# projet666.net
KiCad netlist of a schematic drawn in EasyEDA Pro
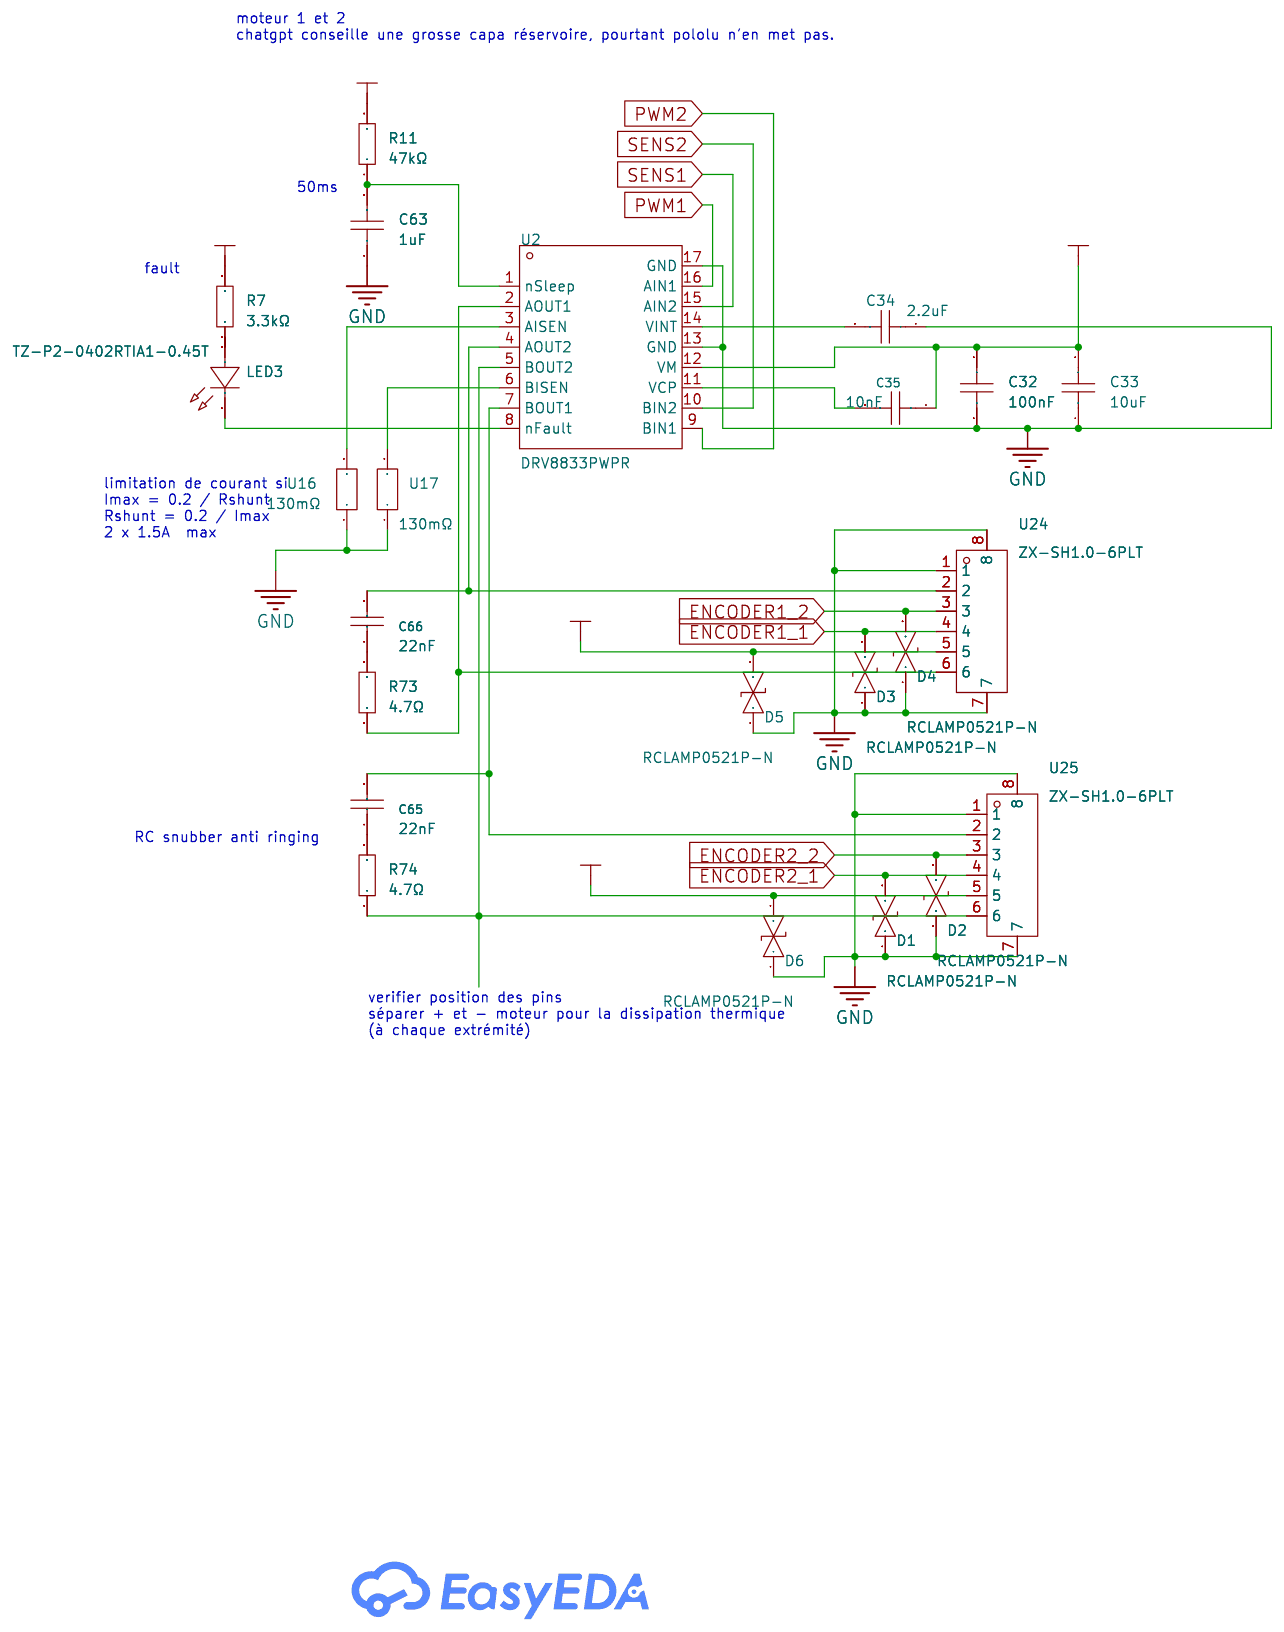
[diagram p0: Pont + connecteurs]
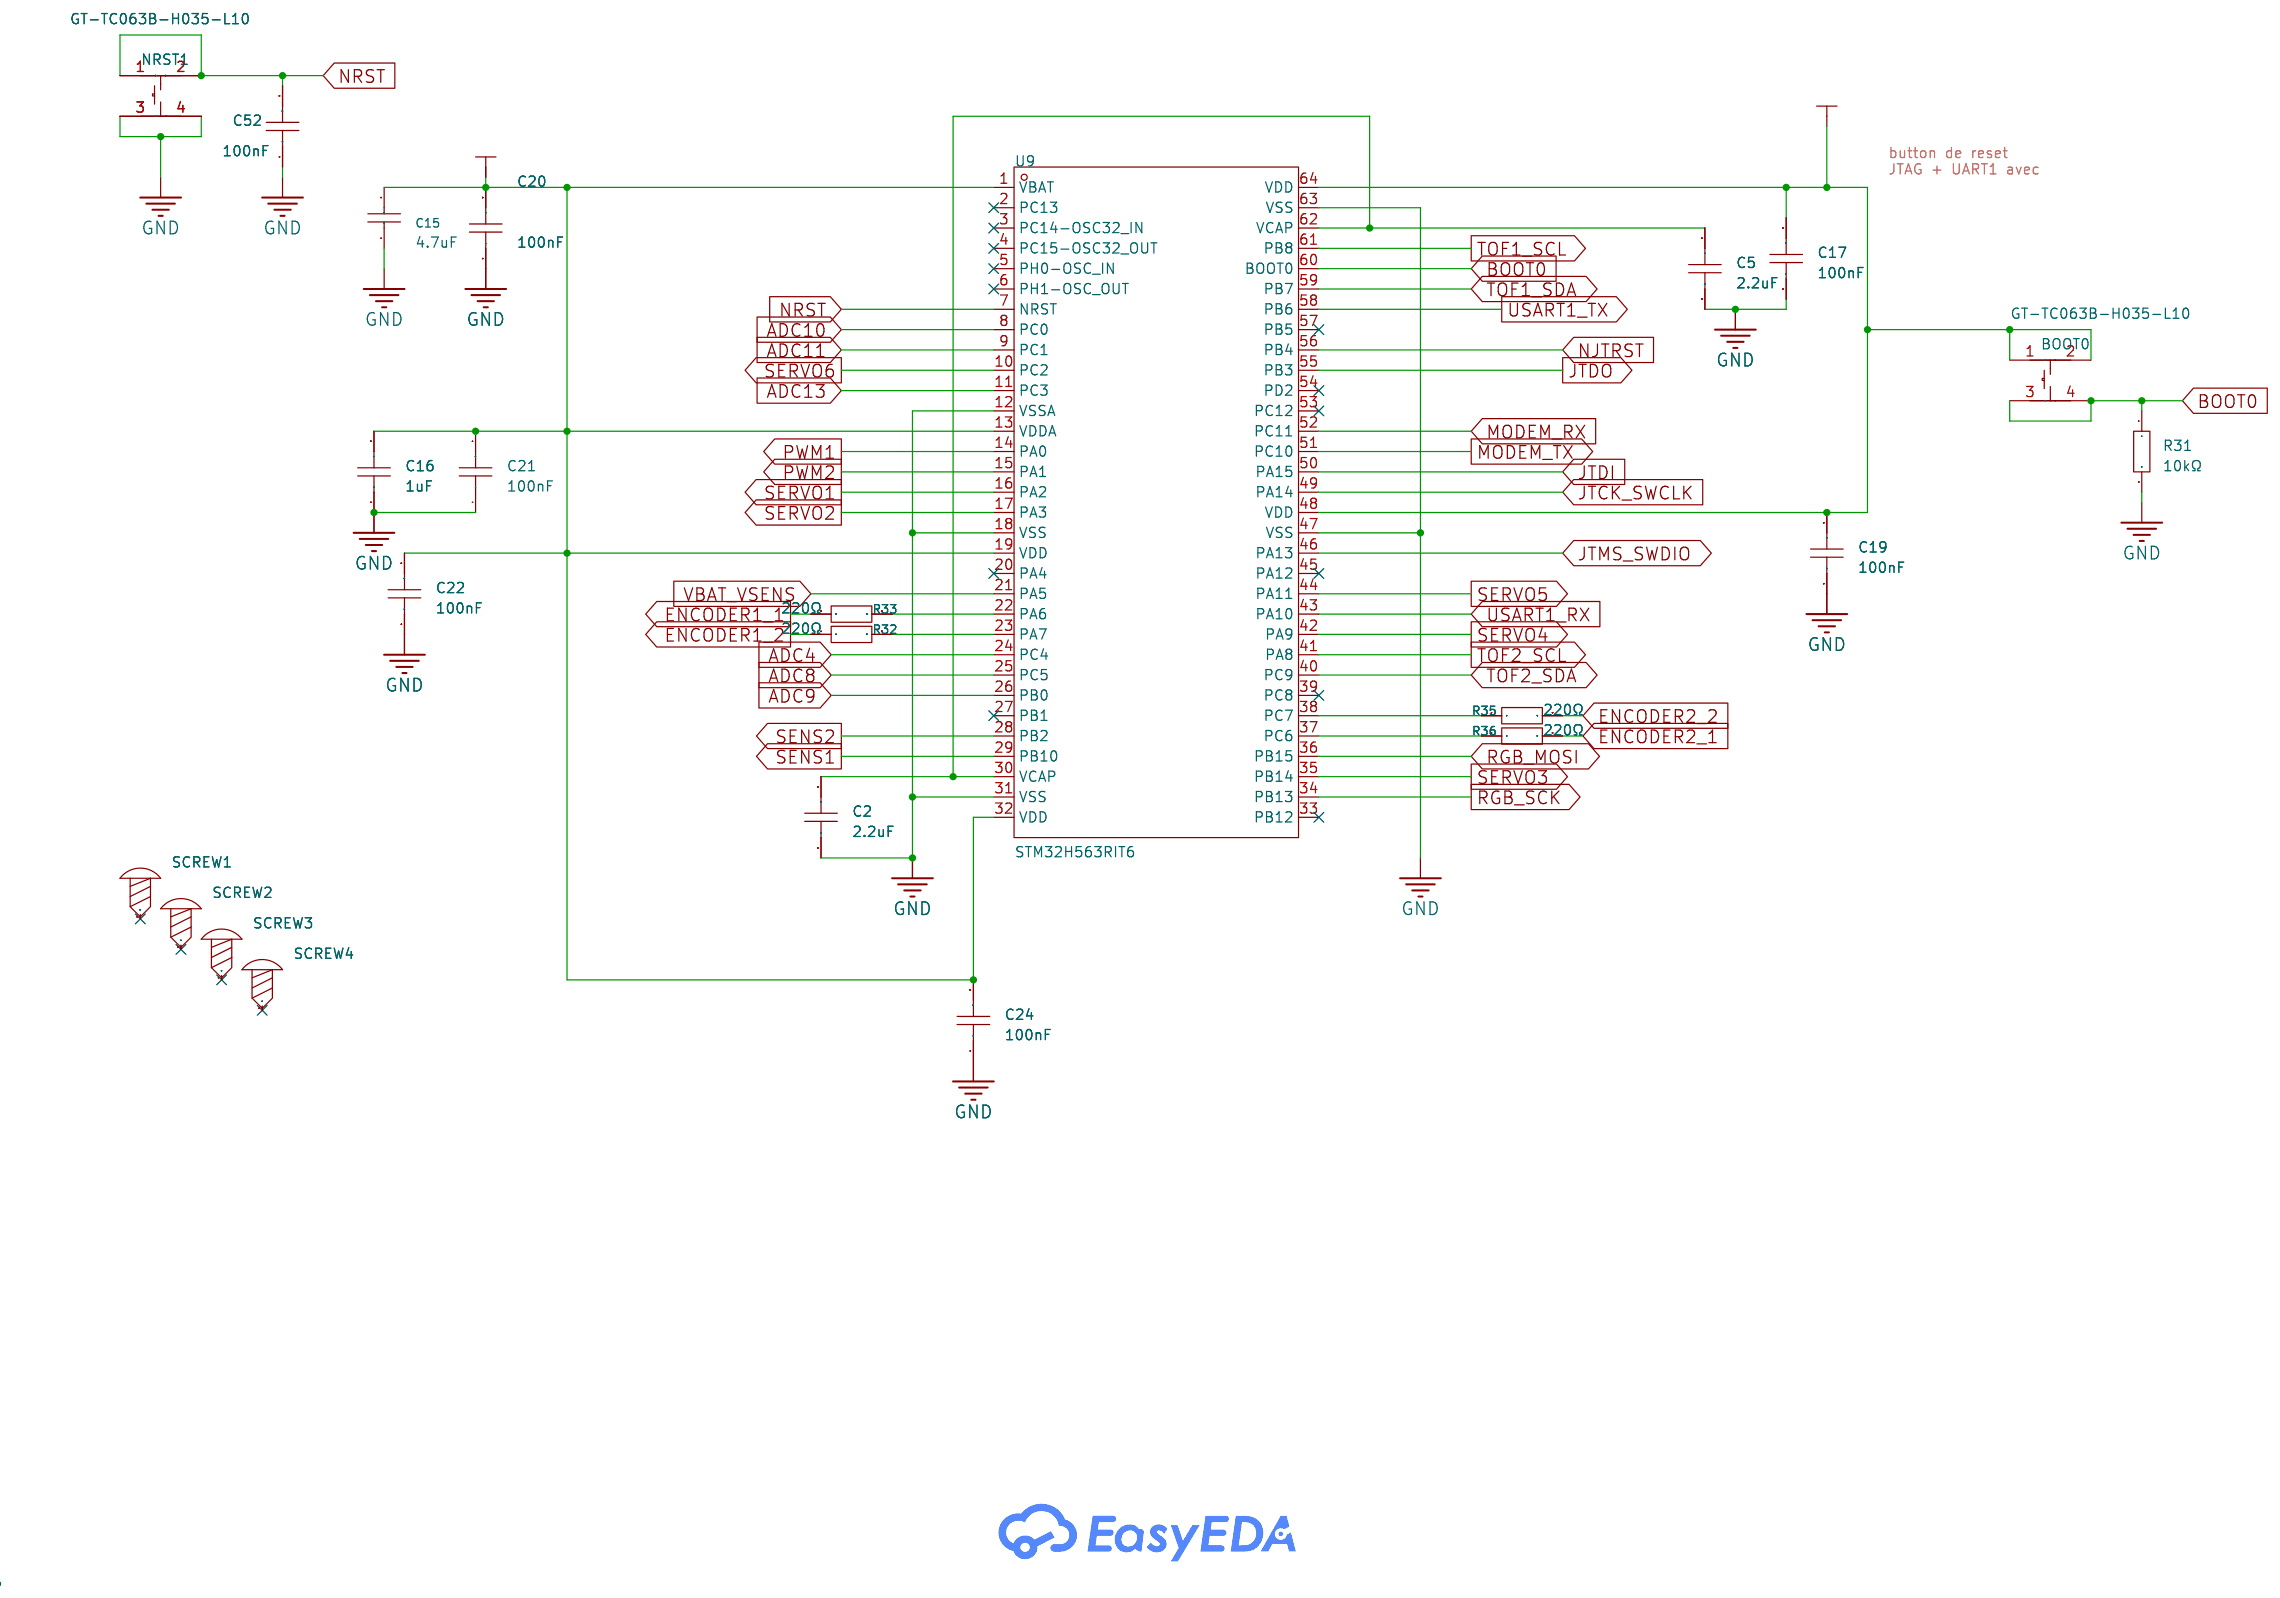
[diagram p1: stm32]
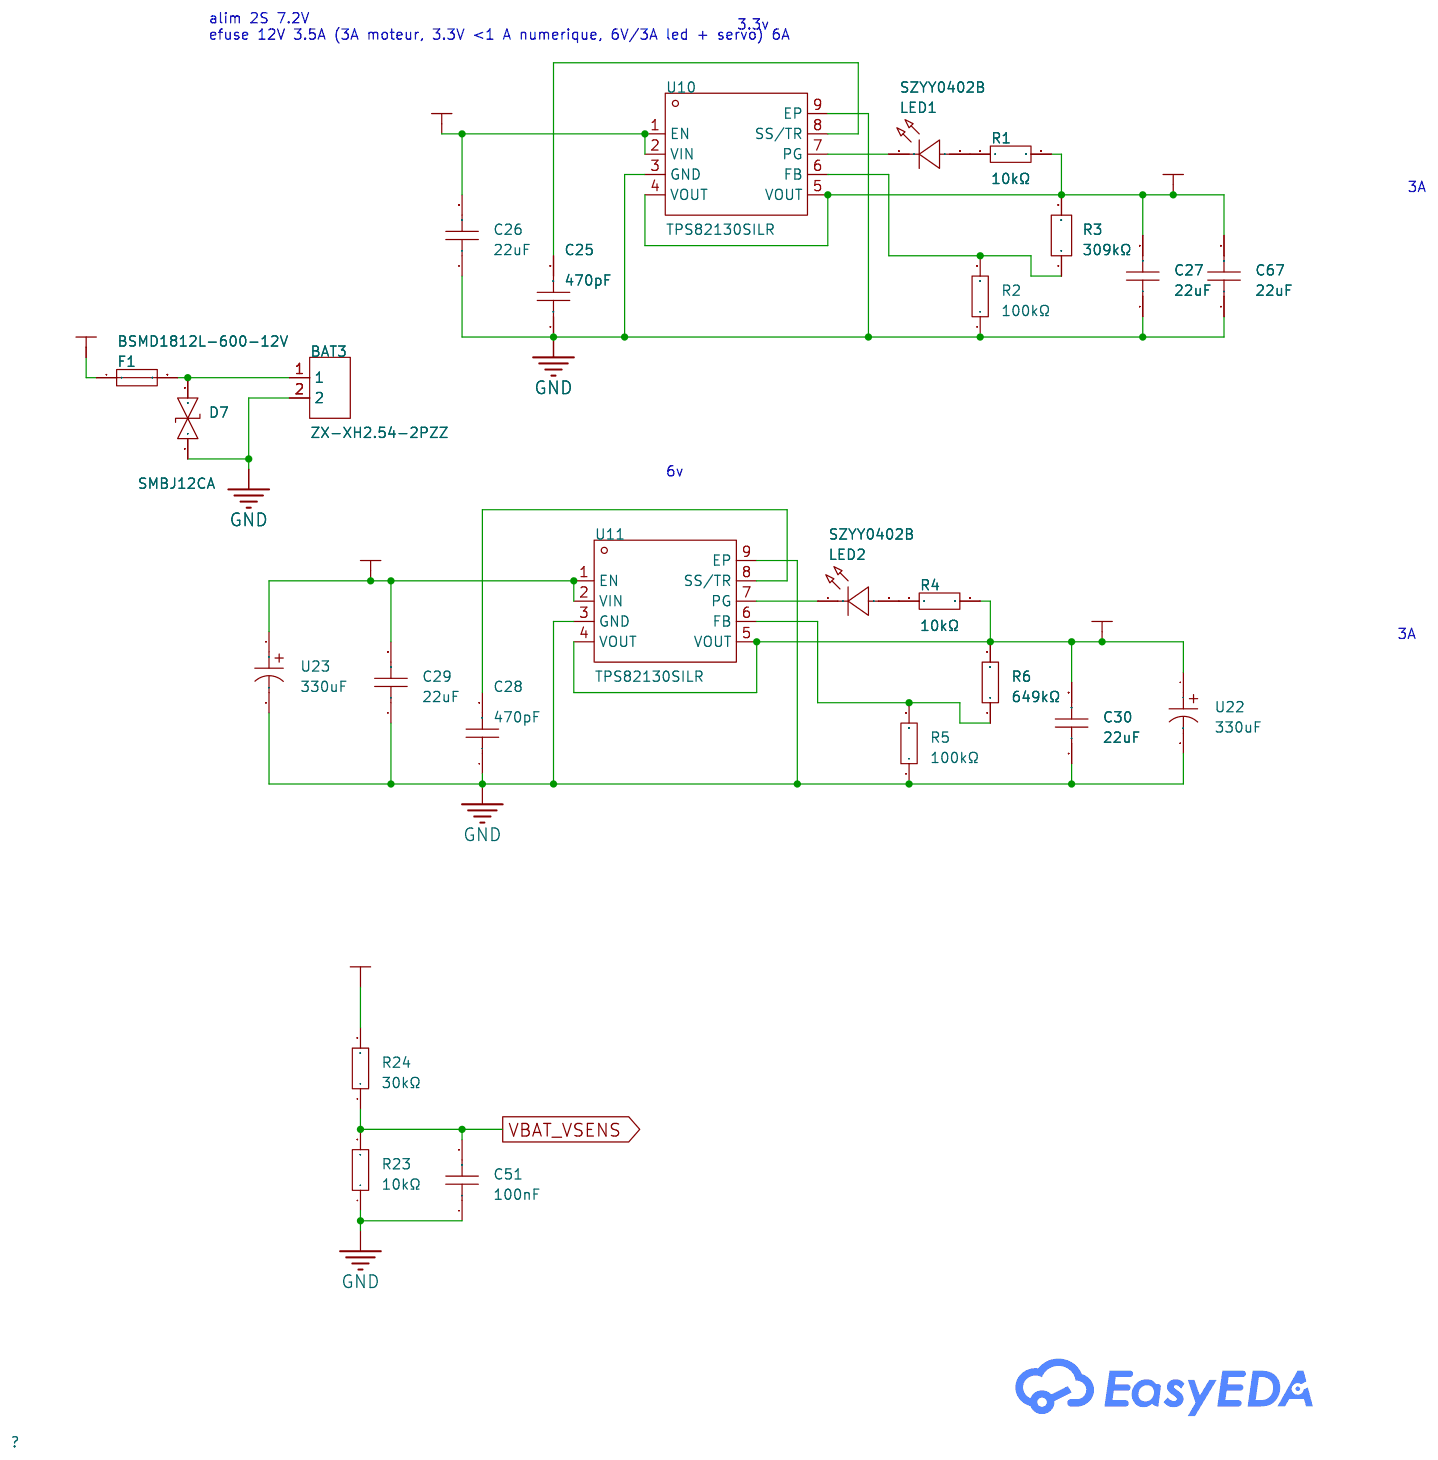
[diagram p2: alim]
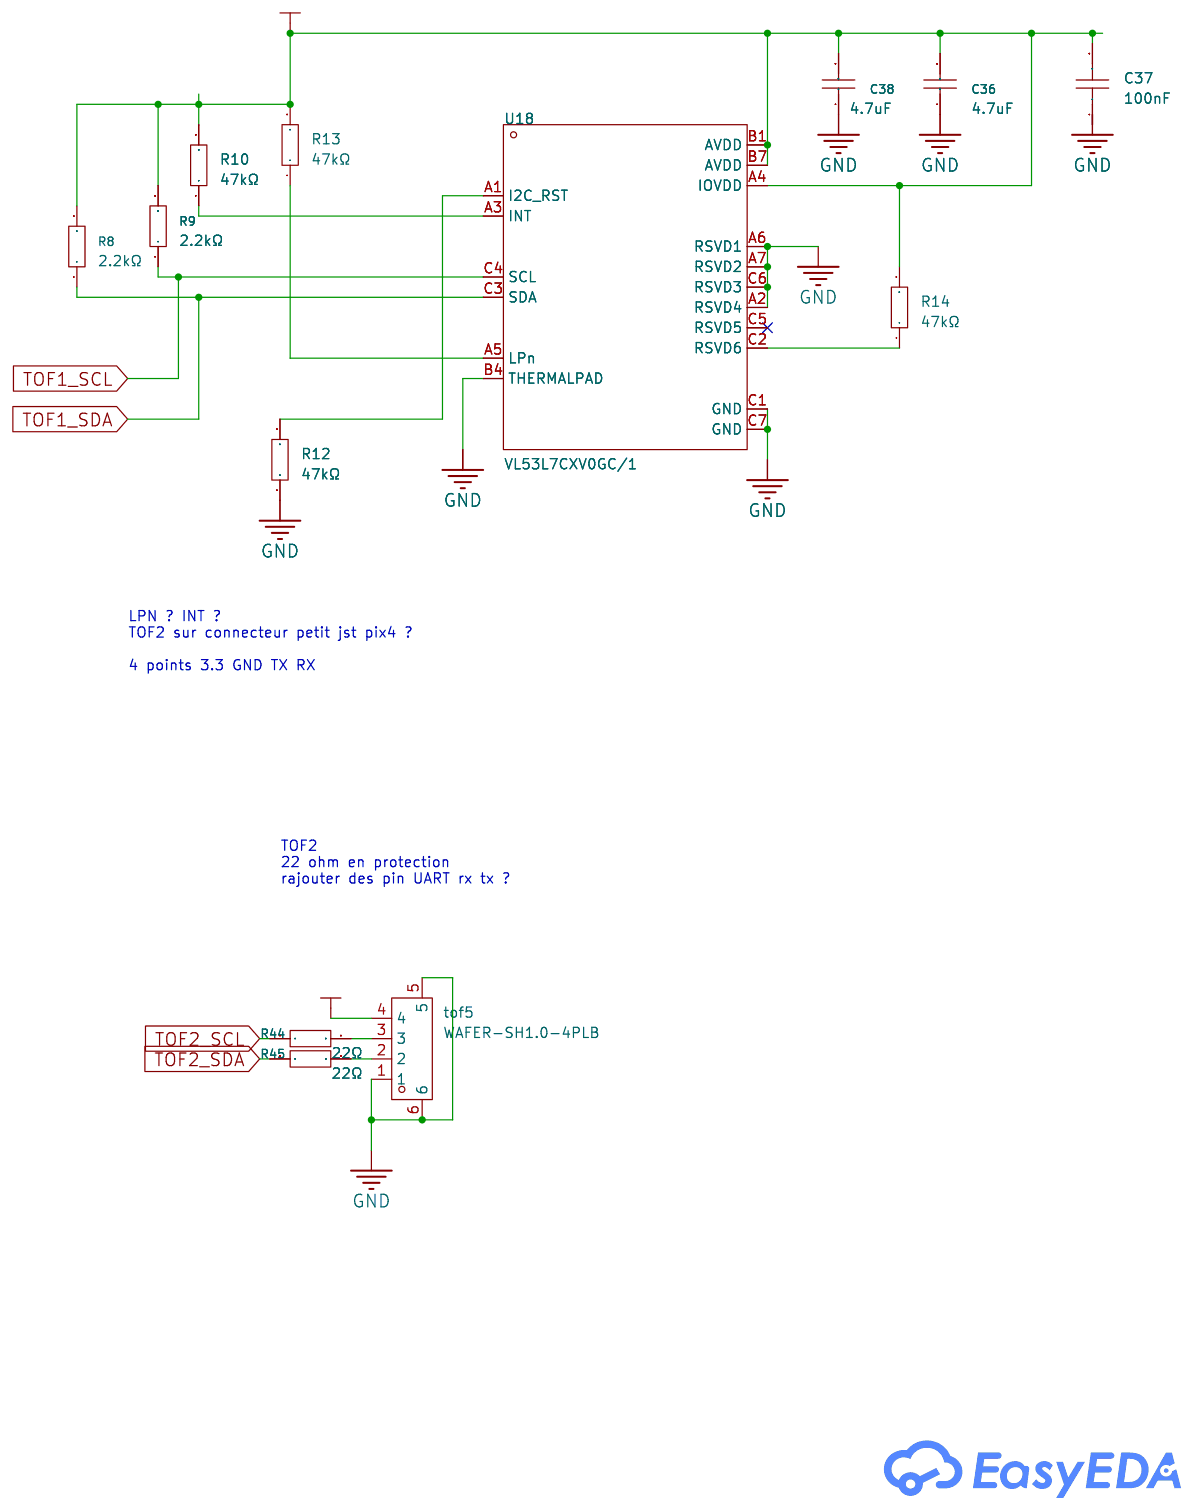
[diagram p3: tof]
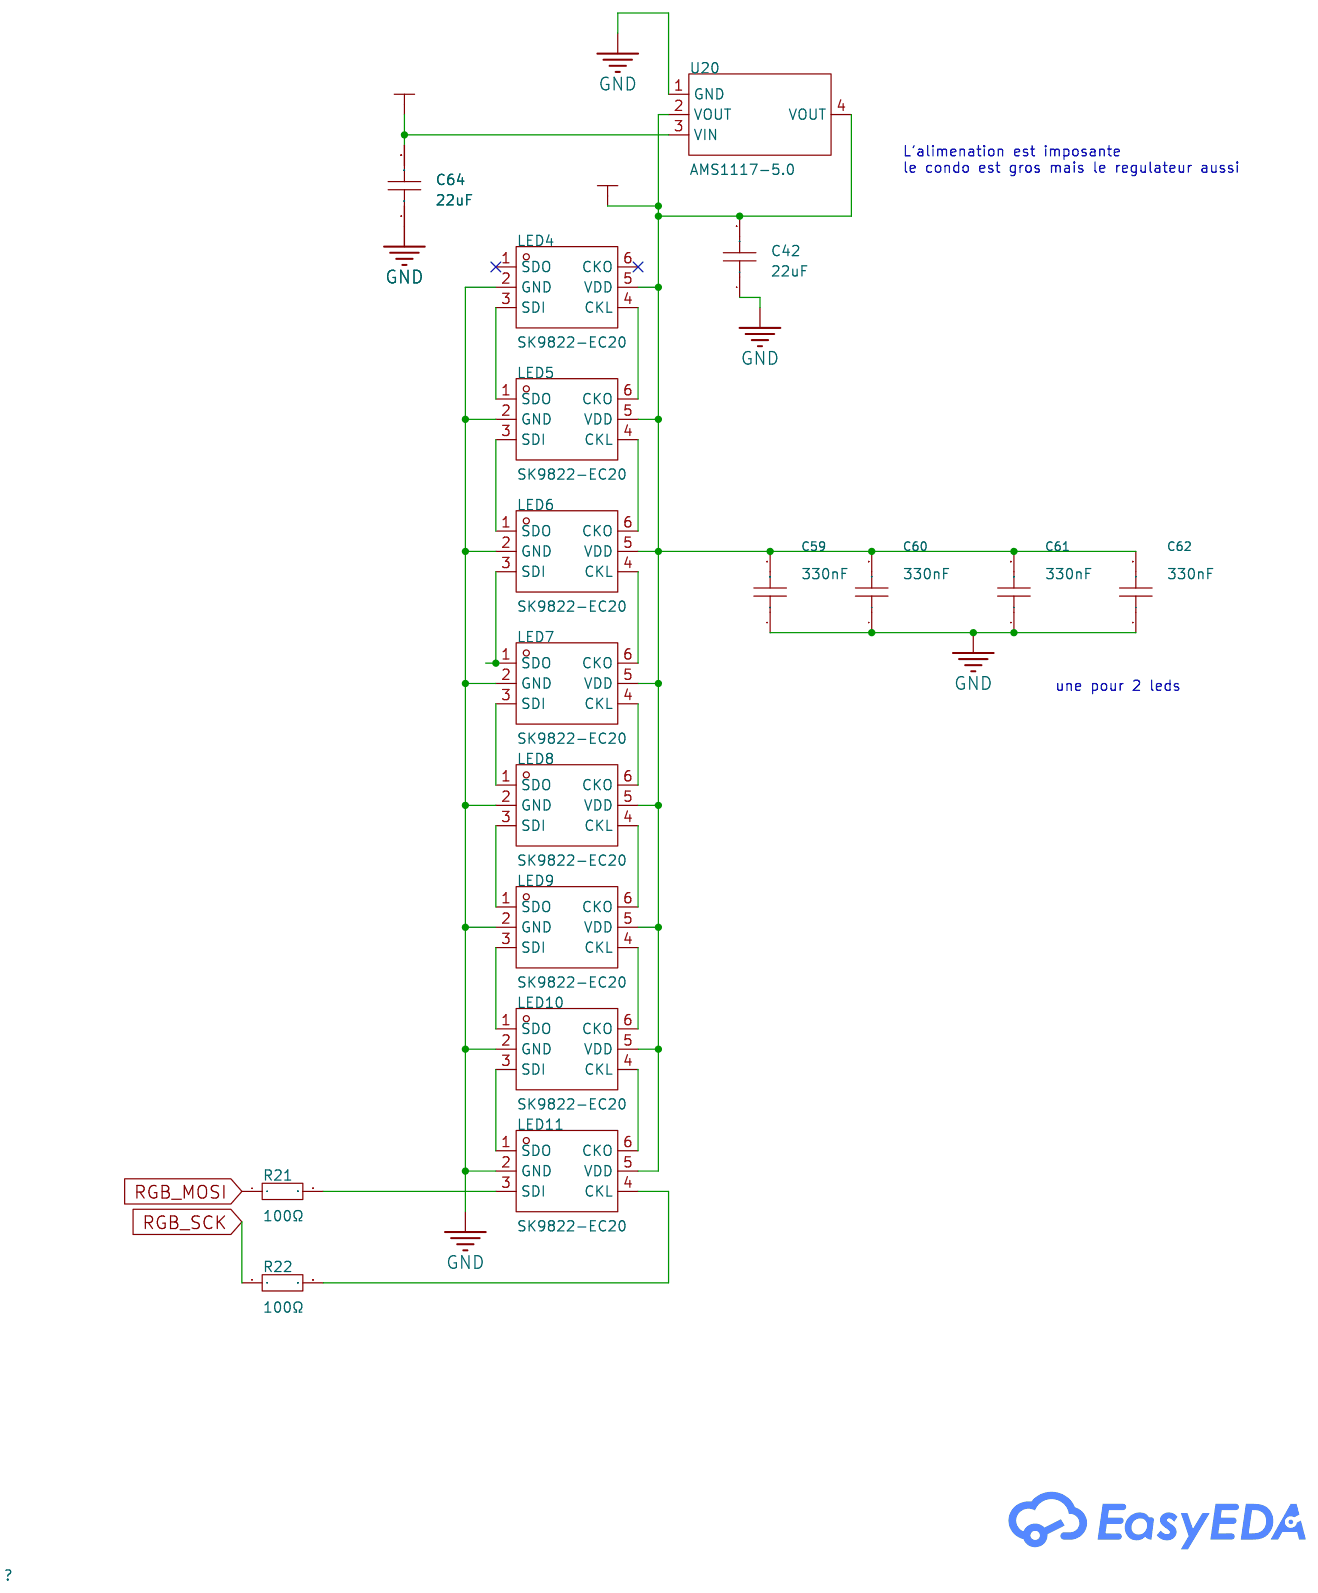
[diagram p4: leds]
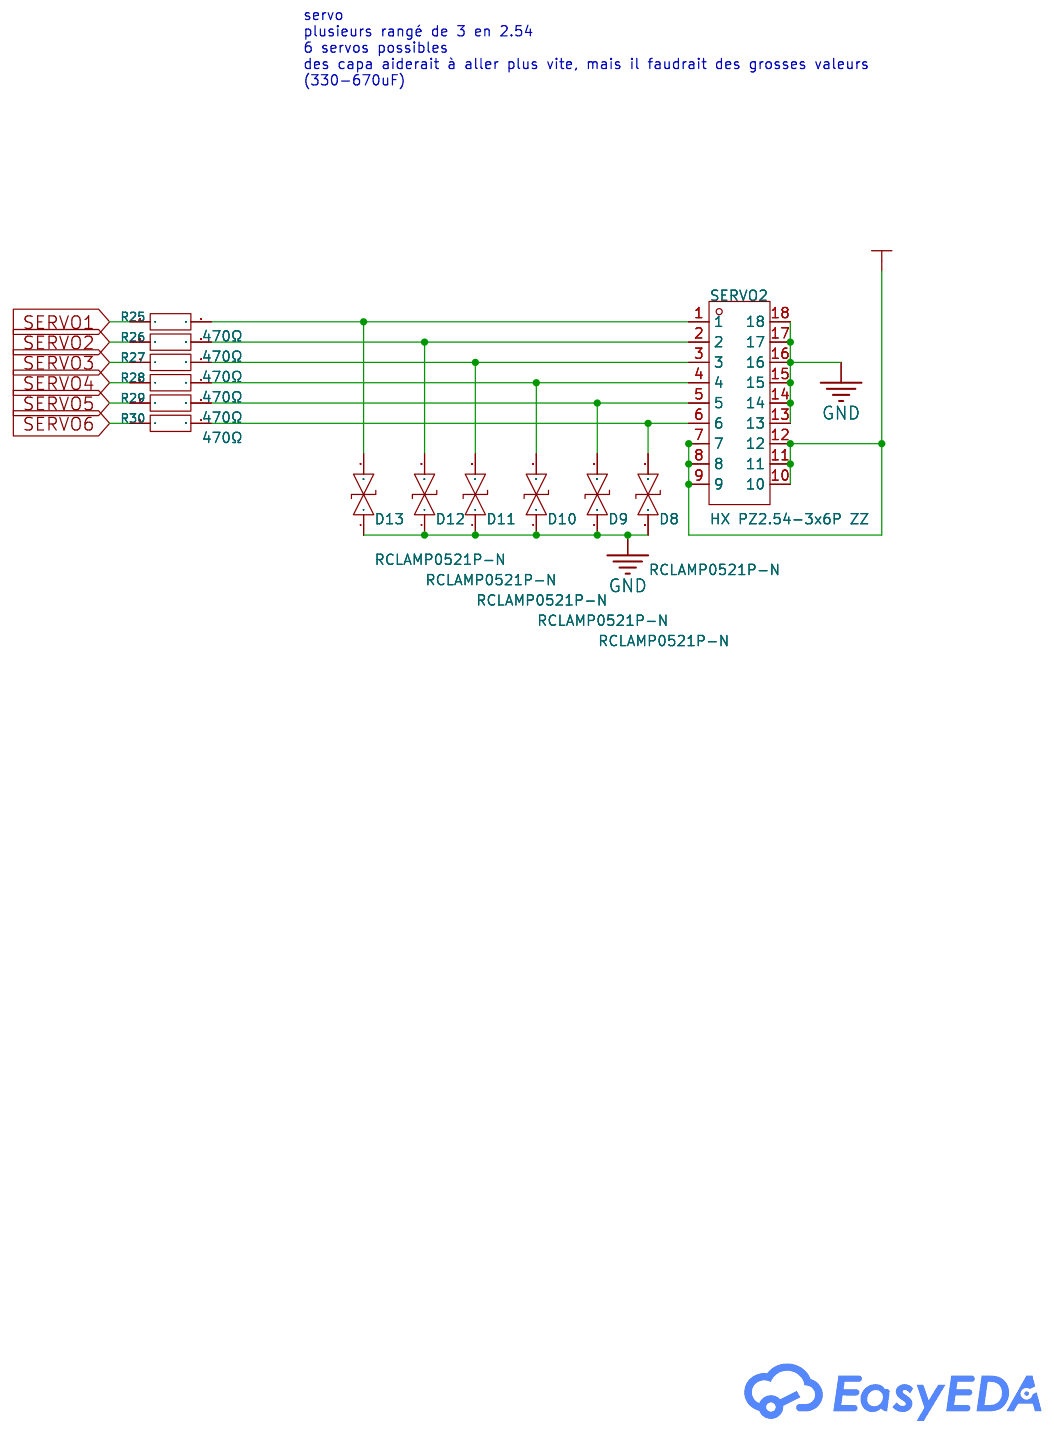
[diagram p5: servo]
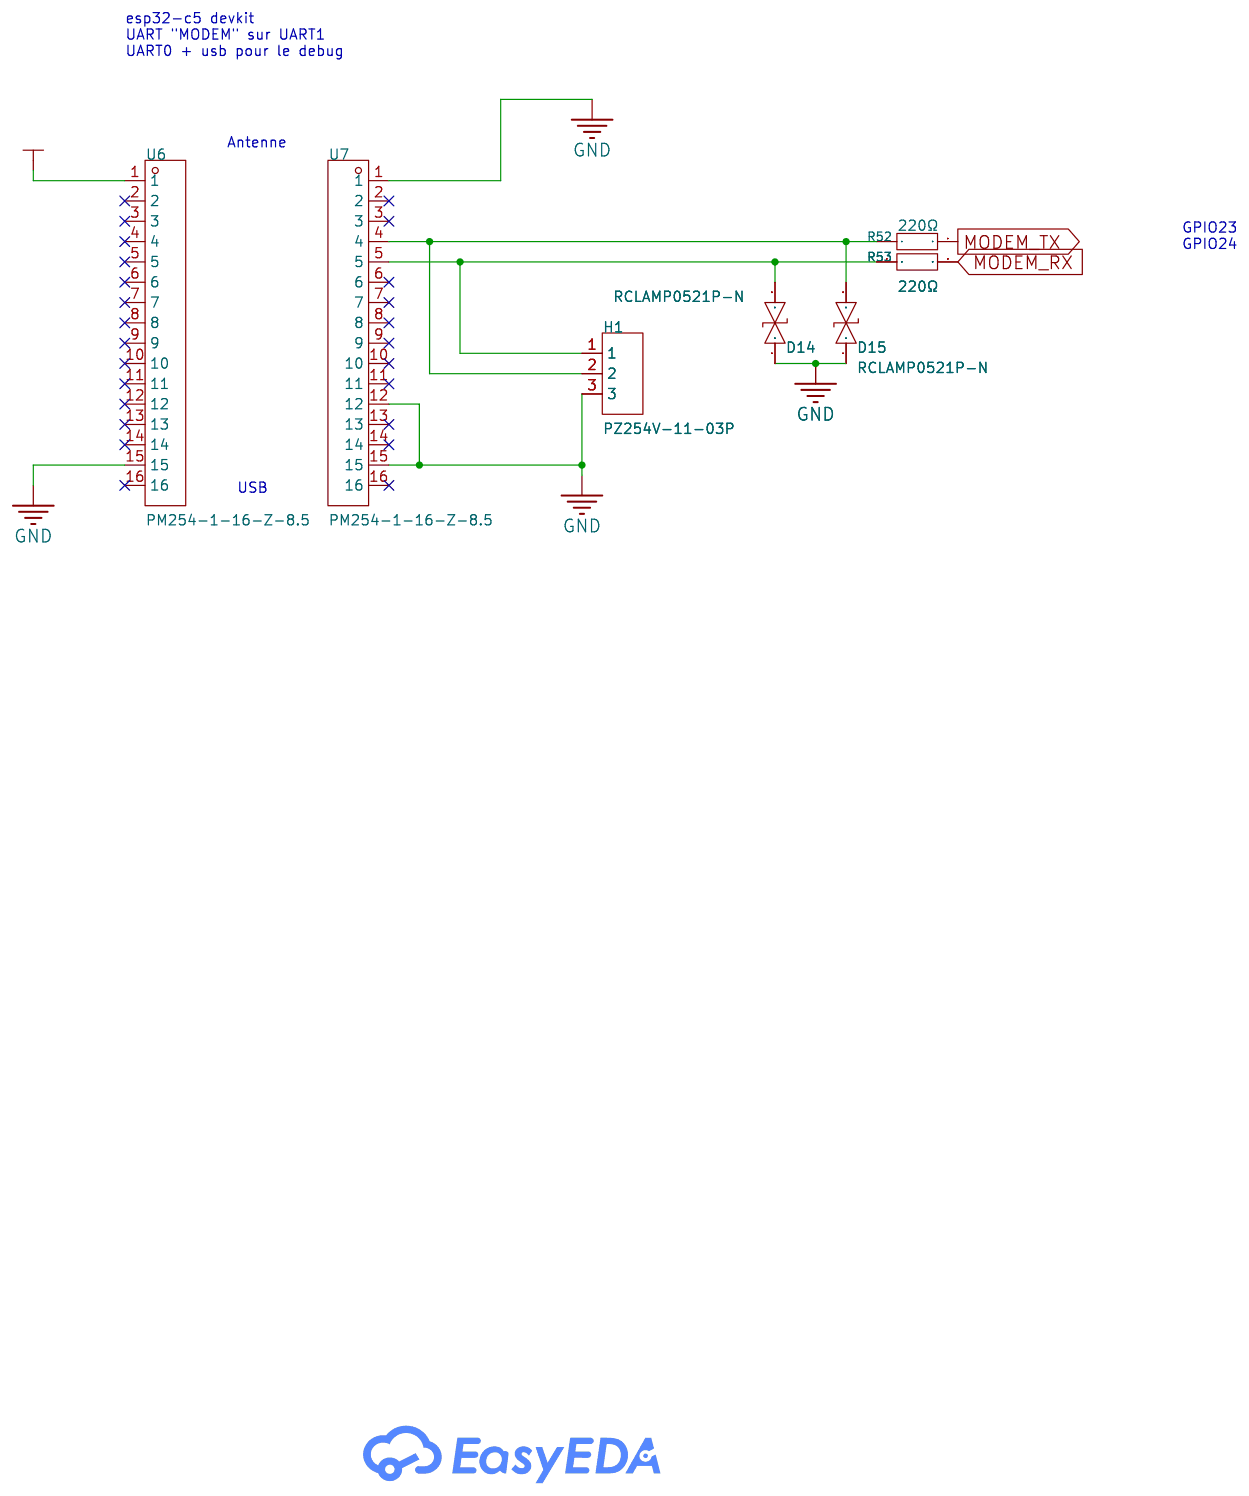
[diagram p6: esp32]
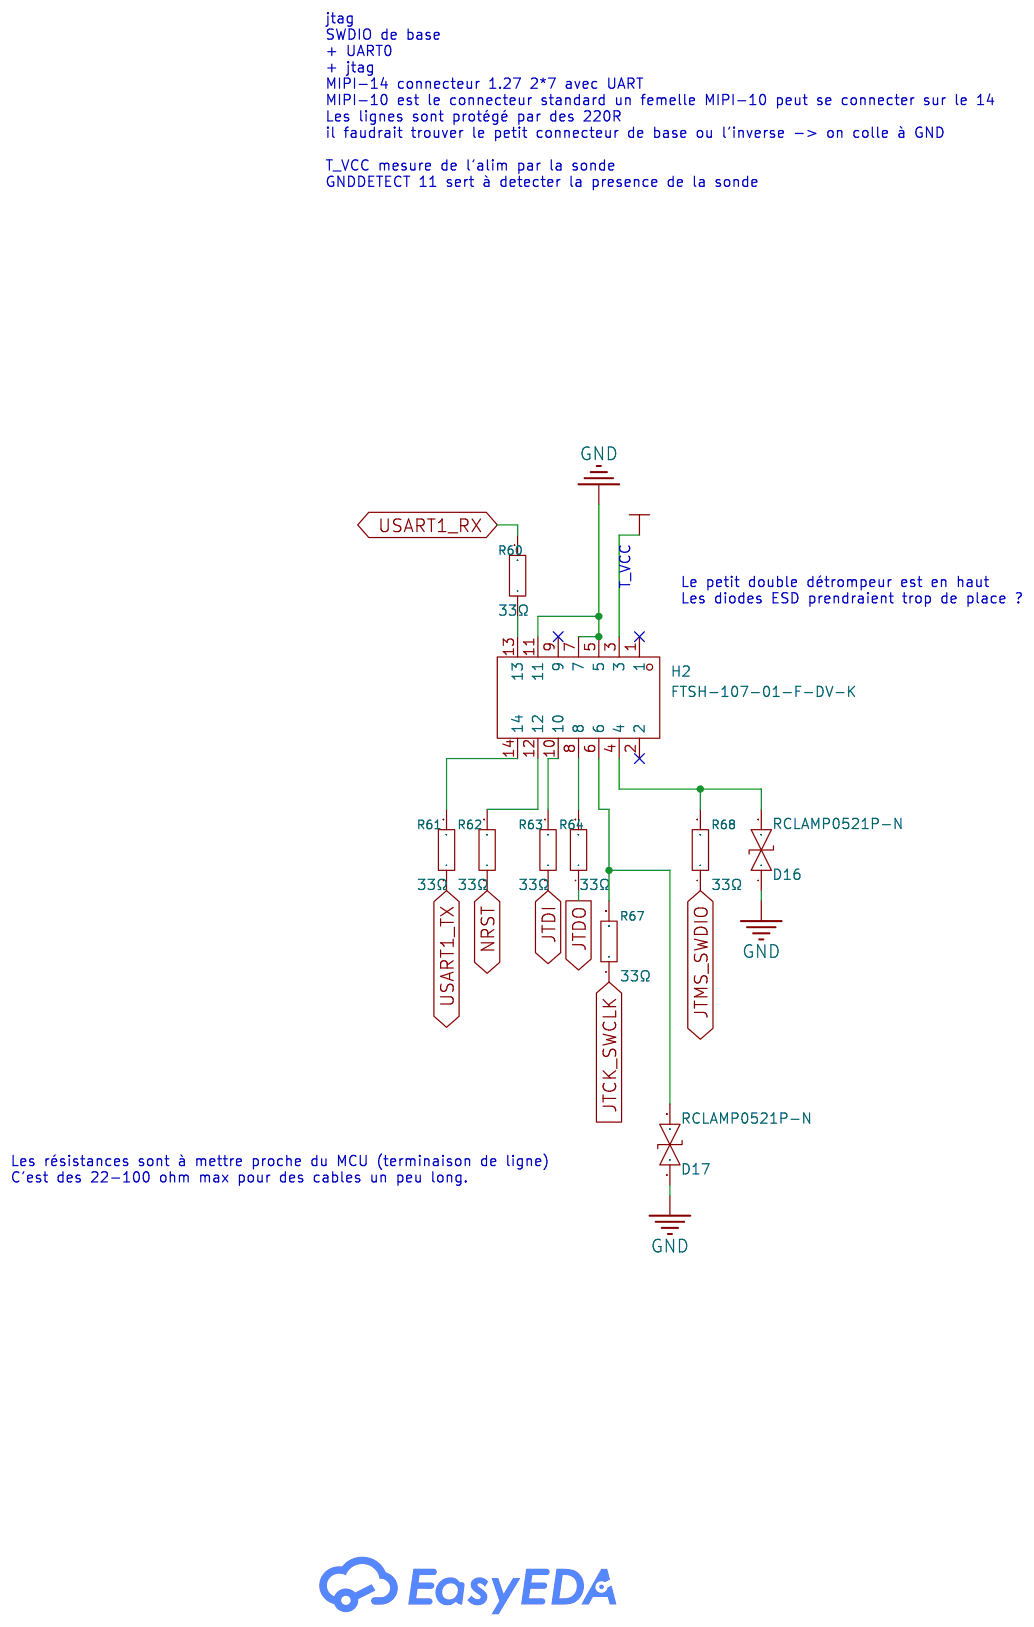
[diagram p7: jtag]
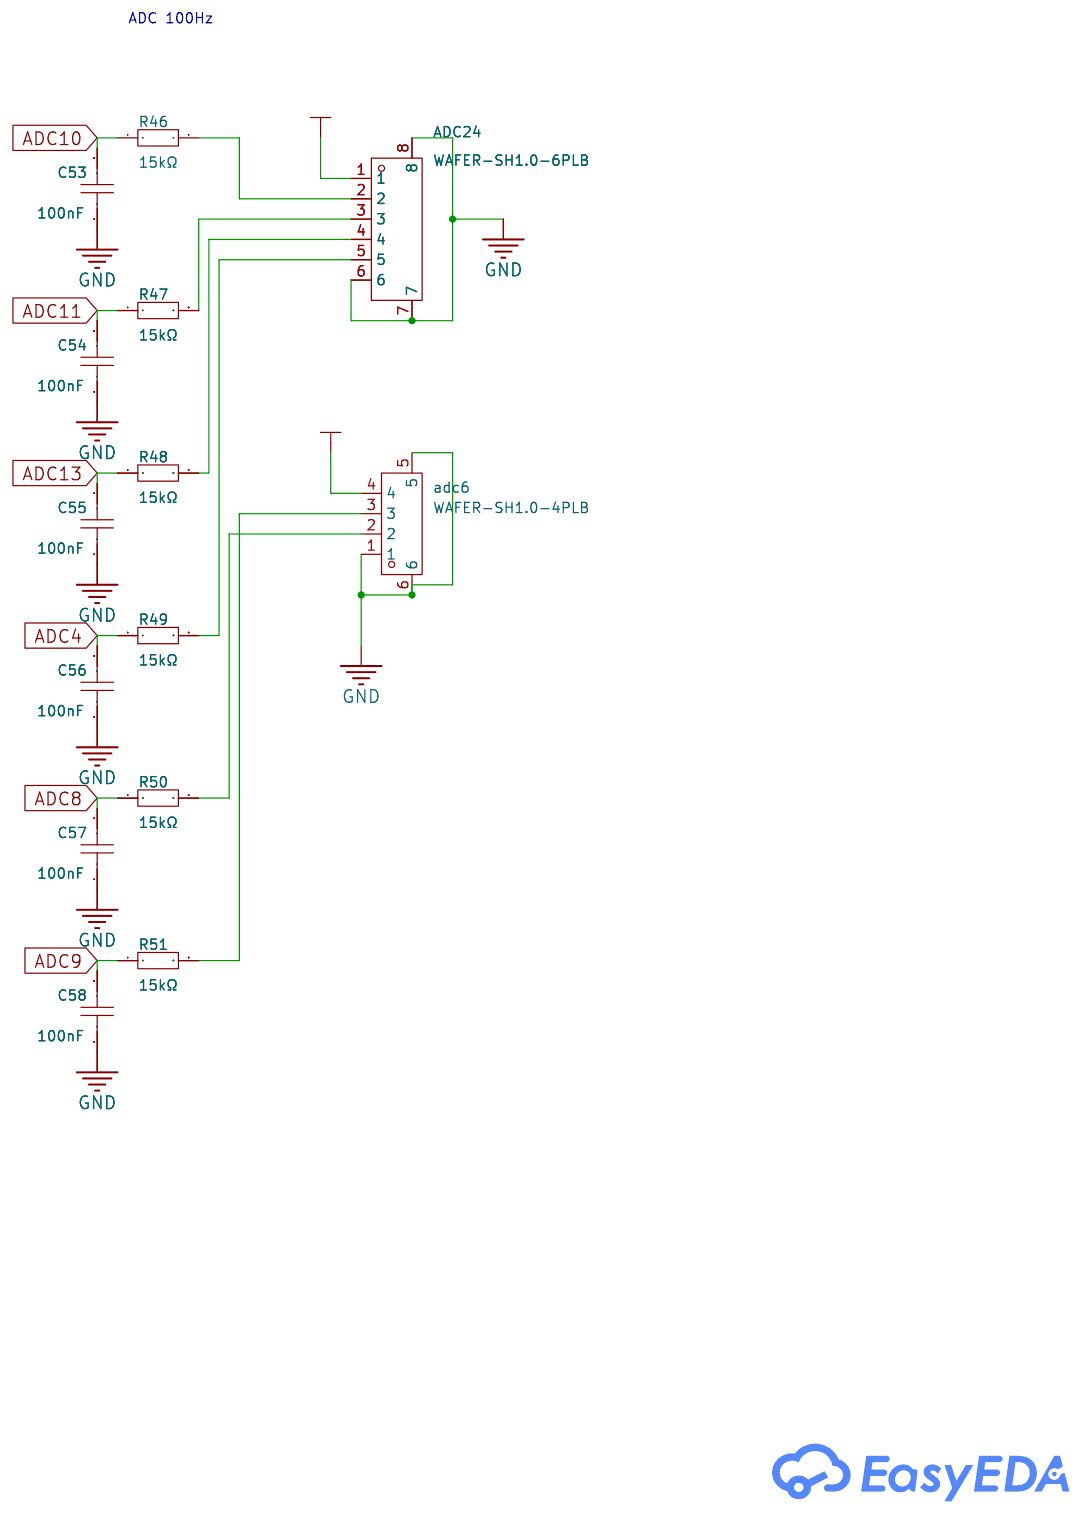
[diagram p8: ADC]

(export (version "E")
  (design (tool "Eeschema 10.0.6"))
  (components
    (comp (ref "C32")
      (value "100nF")
      (footprint "easyedapro:C0201")
      (description "Capacitance:100nF Tolerance:±10% Tolerance:±10% Voltage Rating:16V Temperature Coefficient:X5R")
      (fields (field (name "Manufacturer Part") "0201X104K160NT") (field (name "Manufacturer") "FH(风华)"))
      (libsource (lib "easyedapro") (part "0201X104K160NT"))
    )
    (comp (ref "C33")
      (value "10uF")
      (footprint "easyedapro:C0805")
      (fields
        (field (name "Manufacturer Part") "CL21A106KAYNNNE")
        (field (name "Manufacturer") "SAMSUNG(三星)")
      )
      (libsource (lib "easyedapro") (part "CL21A106KAYNNNE"))
    )
    (comp (ref "C34")
      (value "2.2uF")
      (footprint "easyedapro:C0402")
      (fields
        (field (name "Manufacturer Part") "CL05A225KO5NQNC")
        (field (name "Manufacturer") "SAMSUNG(三星)")
      )
      (libsource (lib "easyedapro") (part "CL05A225KO5NQNC"))
    )
    (comp (ref "C35")
      (value "10nF")
      (footprint "easyedapro:C0201")
      (fields
        (field (name "Manufacturer Part") "GRM033R71E103KE14D")
        (field (name "Manufacturer") "muRata(村田)")
      )
      (libsource (lib "easyedapro") (part "GRM033R71E103KE14D"))
    )
    (comp (ref "C63")
      (value "1uF")
      (footprint "easyedapro:C0402")
      (fields
        (field (name "Manufacturer Part") "CL05A105KA5NQNC")
        (field (name "Manufacturer") "SAMSUNG(三星)")
      )
      (libsource (lib "easyedapro") (part "CL05A105KA5NQNC"))
    )
    (comp (ref "C65")
      (value "22nF")
      (footprint "easyedapro:C0603")
      (description "Capacitance:22nF Tolerance:±10% Tolerance:±10% Voltage Rating:50V Temperature Coefficient:X7R")
      (fields
        (field (name "Manufacturer Part") "CL10B223KB8NNNC")
        (field (name "Manufacturer") "SAMSUNG(三星)")
      )
      (libsource (lib "easyedapro") (part "CL10B223KB8NNNC"))
    )
    (comp (ref "C66")
      (value "22nF")
      (footprint "easyedapro:C0603")
      (description "Capacitance:22nF Tolerance:±10% Tolerance:±10% Voltage Rating:50V Temperature Coefficient:X7R")
      (fields
        (field (name "Manufacturer Part") "CL10B223KB8NNNC")
        (field (name "Manufacturer") "SAMSUNG(三星)")
      )
      (libsource (lib "easyedapro") (part "CL10B223KB8NNNC"))
    )
    (comp (ref "D1")
      (value "RCLAMP0521P-N")
      (footprint "easyedapro:X1-DFN1006-2_L1.0-W0.6-P0.65-BI")
      (fields (field (name "Manufacturer") "BORN(伯恩半导体)"))
      (libsource (lib "easyedapro") (part "RCLAMP0521P-N"))
    )
    (comp (ref "D2")
      (value "RCLAMP0521P-N")
      (footprint "easyedapro:X1-DFN1006-2_L1.0-W0.6-P0.65-BI")
      (fields (field (name "Manufacturer") "BORN(伯恩半导体)"))
      (libsource (lib "easyedapro") (part "RCLAMP0521P-N"))
    )
    (comp (ref "D3")
      (value "RCLAMP0521P-N")
      (footprint "easyedapro:X1-DFN1006-2_L1.0-W0.6-P0.65-BI")
      (fields (field (name "Manufacturer") "BORN(伯恩半导体)"))
      (libsource (lib "easyedapro") (part "RCLAMP0521P-N"))
    )
    (comp (ref "D4")
      (value "RCLAMP0521P-N")
      (footprint "easyedapro:X1-DFN1006-2_L1.0-W0.6-P0.65-BI")
      (fields (field (name "Manufacturer") "BORN(伯恩半导体)"))
      (libsource (lib "easyedapro") (part "RCLAMP0521P-N"))
    )
    (comp (ref "D5")
      (value "RCLAMP0521P-N")
      (footprint "easyedapro:X1-DFN1006-2_L1.0-W0.6-P0.65-BI")
      (fields (field (name "Manufacturer") "BORN(伯恩半导体)"))
      (libsource (lib "easyedapro") (part "RCLAMP0521P-N"))
    )
    (comp (ref "D6")
      (value "RCLAMP0521P-N")
      (footprint "easyedapro:X1-DFN1006-2_L1.0-W0.6-P0.65-BI")
      (fields (field (name "Manufacturer") "BORN(伯恩半导体)"))
      (libsource (lib "easyedapro") (part "RCLAMP0521P-N"))
    )
    (comp (ref "LED3")
      (value "TZ-P2-0402RTIA1-0.45T")
      (footprint "easyedapro:LED0402-RD_RED")
      (fields (field (name "Manufacturer") "TUOZHAN(拓展光电)"))
      (libsource (lib "easyedapro") (part "TZ-P2-0402RTIA1-0.45T"))
    )
    (comp (ref "R7")
      (value "3.3kΩ")
      (footprint "easyedapro:R0402")
      (fields (field (name "Manufacturer Part") "RC0402FR-073K3L") (field (name "Manufacturer") "YAGEO(国巨)"))
      (libsource (lib "easyedapro") (part "RC0402FR-073K3L"))
    )
    (comp (ref "R11")
      (value "47kΩ")
      (footprint "easyedapro:R0402")
      (fields (field (name "Manufacturer Part") "RC0402FR-0747KL") (field (name "Manufacturer") "YAGEO(国巨)"))
      (libsource (lib "easyedapro") (part "RC0402FR-0747KL"))
    )
    (comp (ref "R73")
      (value "4.7Ω")
      (footprint "easyedapro:R0603")
      (fields (field (name "Manufacturer Part") "RC0603FR-074R7L") (field (name "Manufacturer") "YAGEO(国巨)"))
      (libsource (lib "easyedapro") (part "RC0603FR-074R7L"))
    )
    (comp (ref "R74")
      (value "4.7Ω")
      (footprint "easyedapro:R0603")
      (fields (field (name "Manufacturer Part") "RC0603FR-074R7L") (field (name "Manufacturer") "YAGEO(国巨)"))
      (libsource (lib "easyedapro") (part "RC0603FR-074R7L"))
    )
    (comp (ref "U2")
      (value "DRV8833PWPR")
      (footprint "easyedapro:TSSOP-16_L5.0-W4.4-P0.65-LS6.4-BL-EP")
      (description "Technology:Yes Operating Temperature:-40°C~+85°C Operating Temperature:-40°C~+85°C")
      (fields (field (name "Manufacturer") "TI(德州仪器)"))
      (libsource (lib "easyedapro") (part "DRV8833PWP"))
    )
    (comp (ref "U16")
      (value "130mΩ")
      (footprint "easyedapro:R1206")
      (fields
        (field (name "Manufacturer Part") "HoLRT1206-1W-130mR-1%")
        (field (name "Manufacturer") "Milliohm(毫欧)")
      )
      (libsource (lib "easyedapro") (part "HOLRT1206-1W-130MR-1%"))
    )
    (comp (ref "U17")
      (value "130mΩ")
      (footprint "easyedapro:R1206")
      (fields
        (field (name "Manufacturer Part") "HoLRT1206-1W-130mR-1%")
        (field (name "Manufacturer") "Milliohm(毫欧)")
      )
      (libsource (lib "easyedapro") (part "HOLRT1206-1W-130MR-1%"))
    )
    (comp (ref "U24")
      (value "ZX-SH1.0-6PLT")
      (footprint "easyedapro:CONN-SMD_6P-P1.00_ZX-SH1.0-6PLT")
      (fields (field (name "Manufacturer") "Megastar(兆星)"))
      (libsource (lib "easyedapro") (part "ZX-SH1.0-6PLT"))
    )
    (comp (ref "U25")
      (value "ZX-SH1.0-6PLT")
      (footprint "easyedapro:CONN-SMD_6P-P1.00_ZX-SH1.0-6PLT")
      (fields (field (name "Manufacturer") "Megastar(兆星)"))
      (libsource (lib "easyedapro") (part "ZX-SH1.0-6PLT"))
    )
    (comp (ref "BOOT0")
      (value "GT-TC063B-H035-L10")
      (footprint "easyedapro:SW-SMD_4P-L6.2-W6.2-P4.00-LS7.0")
      (fields (field (name "Manufacturer") "G-Switch(品赞)"))
      (libsource (lib "easyedapro") (part "GT-TC063B-H035-L10"))
    )
    (comp (ref "C2")
      (value "2.2uF")
      (footprint "easyedapro:C0402")
      (fields
        (field (name "Manufacturer Part") "CL05A225KO5NQNC")
        (field (name "Manufacturer") "SAMSUNG(三星)")
      )
      (libsource (lib "easyedapro") (part "CL05A225KO5NQNC"))
    )
    (comp (ref "C5")
      (value "2.2uF")
      (footprint "easyedapro:C0402")
      (fields
        (field (name "Manufacturer Part") "CL05A225KO5NQNC")
        (field (name "Manufacturer") "SAMSUNG(三星)")
      )
      (libsource (lib "easyedapro") (part "CL05A225KO5NQNC"))
    )
    (comp (ref "C15")
      (value "4.7uF")
      (footprint "easyedapro:C0402")
      (fields
        (field (name "Manufacturer Part") "CL05A475MP5NRNC")
        (field (name "Manufacturer") "SAMSUNG(三星)")
      )
      (libsource (lib "easyedapro") (part "CL05A475MP5NRNC"))
    )
    (comp (ref "C16")
      (value "1uF")
      (footprint "easyedapro:C0402")
      (fields
        (field (name "Manufacturer Part") "CL05A105KA5NQNC")
        (field (name "Manufacturer") "SAMSUNG(三星)")
      )
      (libsource (lib "easyedapro") (part "CL05A105KA5NQNC"))
    )
    (comp (ref "C17")
      (value "100nF")
      (footprint "easyedapro:C0201")
      (description "Capacitance:100nF Tolerance:±10% Tolerance:±10% Voltage Rating:16V Temperature Coefficient:X5R")
      (fields (field (name "Manufacturer Part") "0201X104K160NT") (field (name "Manufacturer") "FH(风华)"))
      (libsource (lib "easyedapro") (part "0201X104K160NT"))
    )
    (comp (ref "C19")
      (value "100nF")
      (footprint "easyedapro:C0201")
      (description "Capacitance:100nF Tolerance:±10% Tolerance:±10% Voltage Rating:16V Temperature Coefficient:X5R")
      (fields (field (name "Manufacturer Part") "0201X104K160NT") (field (name "Manufacturer") "FH(风华)"))
      (libsource (lib "easyedapro") (part "0201X104K160NT"))
    )
    (comp (ref "C20")
      (value "100nF")
      (footprint "easyedapro:C0201")
      (description "Capacitance:100nF Tolerance:±10% Tolerance:±10% Voltage Rating:16V Temperature Coefficient:X5R")
      (fields (field (name "Manufacturer Part") "0201X104K160NT") (field (name "Manufacturer") "FH(风华)"))
      (libsource (lib "easyedapro") (part "0201X104K160NT"))
    )
    (comp (ref "C21")
      (value "100nF")
      (footprint "easyedapro:C0201")
      (description "Capacitance:100nF Tolerance:±10% Tolerance:±10% Voltage Rating:16V Temperature Coefficient:X5R")
      (fields (field (name "Manufacturer Part") "0201X104K160NT") (field (name "Manufacturer") "FH(风华)"))
      (libsource (lib "easyedapro") (part "0201X104K160NT"))
    )
    (comp (ref "C22")
      (value "100nF")
      (footprint "easyedapro:C0201")
      (description "Capacitance:100nF Tolerance:±10% Tolerance:±10% Voltage Rating:16V Temperature Coefficient:X5R")
      (fields (field (name "Manufacturer Part") "0201X104K160NT") (field (name "Manufacturer") "FH(风华)"))
      (libsource (lib "easyedapro") (part "0201X104K160NT"))
    )
    (comp (ref "C24")
      (value "100nF")
      (footprint "easyedapro:C0201")
      (description "Capacitance:100nF Tolerance:±10% Tolerance:±10% Voltage Rating:16V Temperature Coefficient:X5R")
      (fields (field (name "Manufacturer Part") "0201X104K160NT") (field (name "Manufacturer") "FH(风华)"))
      (libsource (lib "easyedapro") (part "0201X104K160NT"))
    )
    (comp (ref "C52")
      (value "100nF")
      (footprint "easyedapro:C0201")
      (description "Capacitance:100nF Tolerance:±10% Tolerance:±10% Voltage Rating:16V Temperature Coefficient:X5R")
      (fields (field (name "Manufacturer Part") "0201X104K160NT") (field (name "Manufacturer") "FH(风华)"))
      (libsource (lib "easyedapro") (part "0201X104K160NT"))
    )
    (comp (ref "NRST1")
      (value "GT-TC063B-H035-L10")
      (footprint "easyedapro:SW-SMD_4P-L6.2-W6.2-P4.00-LS7.0")
      (fields (field (name "Manufacturer") "G-Switch(品赞)"))
      (libsource (lib "easyedapro") (part "GT-TC063B-H035-L10"))
    )
    (comp (ref "R31")
      (value "10kΩ")
      (footprint "easyedapro:R0402")
      (fields (field (name "Manufacturer Part") "RC0402FR-0710KL") (field (name "Manufacturer") "YAGEO(国巨)"))
      (libsource (lib "easyedapro") (part "RC0402FR-0710KL"))
    )
    (comp (ref "R32")
      (value "220Ω")
      (footprint "easyedapro:R0603")
      (fields
        (field (name "Manufacturer Part") "0603WAF2200T5E")
        (field (name "Manufacturer") "UNI-ROYAL(厚声)")
      )
      (libsource (lib "easyedapro") (part "0603WAF2200T5E"))
    )
    (comp (ref "R33")
      (value "220Ω")
      (footprint "easyedapro:R0603")
      (fields
        (field (name "Manufacturer Part") "0603WAF2200T5E")
        (field (name "Manufacturer") "UNI-ROYAL(厚声)")
      )
      (libsource (lib "easyedapro") (part "0603WAF2200T5E"))
    )
    (comp (ref "R35")
      (value "220Ω")
      (footprint "easyedapro:R0603")
      (fields
        (field (name "Manufacturer Part") "0603WAF2200T5E")
        (field (name "Manufacturer") "UNI-ROYAL(厚声)")
      )
      (libsource (lib "easyedapro") (part "0603WAF2200T5E"))
    )
    (comp (ref "R36")
      (value "220Ω")
      (footprint "easyedapro:R0603")
      (fields
        (field (name "Manufacturer Part") "0603WAF2200T5E")
        (field (name "Manufacturer") "UNI-ROYAL(厚声)")
      )
      (libsource (lib "easyedapro") (part "0603WAF2200T5E"))
    )
    (comp (ref "SCREW1")
      (value "~")
      (footprint "easyedapro:Screw-Hole-M2")
      (libsource (lib "easyedapro") (part "Screw-Hole"))
    )
    (comp (ref "SCREW2")
      (value "~")
      (footprint "easyedapro:Screw-Hole-M2")
      (libsource (lib "easyedapro") (part "Screw-Hole"))
    )
    (comp (ref "SCREW3")
      (value "~")
      (footprint "easyedapro:Screw-Hole-M2")
      (libsource (lib "easyedapro") (part "Screw-Hole"))
    )
    (comp (ref "SCREW4")
      (value "~")
      (footprint "easyedapro:Screw-Hole-M2")
      (libsource (lib "easyedapro") (part "Screw-Hole"))
    )
    (comp (ref "U9")
      (value "STM32H563RIT6")
      (footprint "easyedapro:LQFP-64_L10.0-W10.0-P0.50-LS12.0-BL")
      (fields (field (name "Manufacturer") "ST(意法半导体)"))
      (libsource (lib "easyedapro") (part "STM32H563RIT6"))
    )
    (comp (ref "BAT3")
      (value "ZX-XH2.54-2PZZ")
      (footprint "easyedapro:CONN-TH_2P-P2.50_HX25003-2A")
      (fields (field (name "Manufacturer") "Megastar(兆星)"))
      (libsource (lib "easyedapro") (part "ZX-XH2.54-2PZZ"))
    )
    (comp (ref "C25")
      (value "470pF")
      (footprint "easyedapro:C0201")
      (description "Capacitance:470pF Tolerance:±5% Tolerance:±5% Voltage Rating:25V Temperature Coefficient:C0G")
      (fields
        (field (name "Manufacturer Part") "GRM0335C1E471JA01D")
        (field (name "Manufacturer") "muRata(村田)")
      )
      (libsource (lib "easyedapro") (part "GRM0335C1E471JA01D"))
    )
    (comp (ref "C26")
      (value "22uF")
      (footprint "easyedapro:C0805")
      (fields
        (field (name "Manufacturer Part") "CL21A226MAYNNNE")
        (field (name "Manufacturer") "SAMSUNG(三星)")
      )
      (libsource (lib "easyedapro") (part "CL21A226MAYNNNE"))
    )
    (comp (ref "C27")
      (value "22uF")
      (footprint "easyedapro:C0805")
      (fields
        (field (name "Manufacturer Part") "CL21A226MAYNNNE")
        (field (name "Manufacturer") "SAMSUNG(三星)")
      )
      (libsource (lib "easyedapro") (part "CL21A226MAYNNNE"))
    )
    (comp (ref "C28")
      (value "470pF")
      (footprint "easyedapro:C0201")
      (description "Capacitance:470pF Tolerance:±5% Tolerance:±5% Voltage Rating:25V Temperature Coefficient:C0G")
      (fields
        (field (name "Manufacturer Part") "GRM0335C1E471JA01D")
        (field (name "Manufacturer") "muRata(村田)")
      )
      (libsource (lib "easyedapro") (part "GRM0335C1E471JA01D"))
    )
    (comp (ref "C29")
      (value "22uF")
      (footprint "easyedapro:C0805")
      (fields
        (field (name "Manufacturer Part") "CL21A226MAYNNNE")
        (field (name "Manufacturer") "SAMSUNG(三星)")
      )
      (libsource (lib "easyedapro") (part "CL21A226MAYNNNE"))
    )
    (comp (ref "C30")
      (value "22uF")
      (footprint "easyedapro:C0805")
      (fields
        (field (name "Manufacturer Part") "CL21A226MAYNNNE")
        (field (name "Manufacturer") "SAMSUNG(三星)")
      )
      (libsource (lib "easyedapro") (part "CL21A226MAYNNNE"))
    )
    (comp (ref "C51")
      (value "100nF")
      (footprint "easyedapro:C0201")
      (description "Capacitance:100nF Tolerance:±10% Tolerance:±10% Voltage Rating:16V Temperature Coefficient:X5R")
      (fields (field (name "Manufacturer Part") "0201X104K160NT") (field (name "Manufacturer") "FH(风华)"))
      (libsource (lib "easyedapro") (part "0201X104K160NT"))
    )
    (comp (ref "C67")
      (value "22uF")
      (footprint "easyedapro:C0805")
      (fields
        (field (name "Manufacturer Part") "CL21A226MAYNNNE")
        (field (name "Manufacturer") "SAMSUNG(三星)")
      )
      (libsource (lib "easyedapro") (part "CL21A226MAYNNNE"))
    )
    (comp (ref "D7")
      (value "SMBJ12CA")
      (footprint "easyedapro:SMB_L4.4-W3.6-LS5.3-BI")
      (fields (field (name "Manufacturer") "晶导微电子"))
      (libsource (lib "easyedapro") (part "SMBJ12CA_C353397"))
    )
    (comp (ref "F1")
      (value "BSMD1812L-600-12V")
      (footprint "easyedapro:F1812")
      (fields (field (name "Manufacturer") "BHFUSE(佰宏)"))
      (libsource (lib "easyedapro") (part "BSMD1812L-600-12V"))
    )
    (comp (ref "LED1")
      (value "SZYY0402B")
      (footprint "easyedapro:LED0402-RD_BLUE")
      (fields (field (name "Manufacturer") "yongyu(永裕光电)"))
      (libsource (lib "easyedapro") (part "SZYY0402B"))
    )
    (comp (ref "LED2")
      (value "SZYY0402B")
      (footprint "easyedapro:LED0402-RD_BLUE")
      (fields (field (name "Manufacturer") "yongyu(永裕光电)"))
      (libsource (lib "easyedapro") (part "SZYY0402B"))
    )
    (comp (ref "R1")
      (value "10kΩ")
      (footprint "easyedapro:R0402")
      (fields (field (name "Manufacturer Part") "RC0402FR-0710KL") (field (name "Manufacturer") "YAGEO(国巨)"))
      (libsource (lib "easyedapro") (part "RC0402FR-0710KL"))
    )
    (comp (ref "R2")
      (value "100kΩ")
      (footprint "easyedapro:R0402")
      (fields (field (name "Manufacturer Part") "RC0402FR-07100KL") (field (name "Manufacturer") "YAGEO(国巨)"))
      (libsource (lib "easyedapro") (part "RC0402FR-07100KL"))
    )
    (comp (ref "R3")
      (value "309kΩ")
      (footprint "easyedapro:R0402")
      (fields (field (name "Manufacturer Part") "FRC0402F3093TS") (field (name "Manufacturer") "FOJAN(富捷)"))
      (libsource (lib "easyedapro") (part "FRC0402F3093TS"))
    )
    (comp (ref "R4")
      (value "10kΩ")
      (footprint "easyedapro:R0402")
      (fields (field (name "Manufacturer Part") "RC0402FR-0710KL") (field (name "Manufacturer") "YAGEO(国巨)"))
      (libsource (lib "easyedapro") (part "RC0402FR-0710KL"))
    )
    (comp (ref "R5")
      (value "100kΩ")
      (footprint "easyedapro:R0402")
      (fields (field (name "Manufacturer Part") "RC0402FR-07100KL") (field (name "Manufacturer") "YAGEO(国巨)"))
      (libsource (lib "easyedapro") (part "RC0402FR-07100KL"))
    )
    (comp (ref "R6")
      (value "649kΩ")
      (footprint "easyedapro:R0402")
      (fields
        (field (name "Manufacturer Part") "RMCF0402FT649K")
        (field (name "Manufacturer") "SEI(Stackpole Electronics Inc.)")
      )
      (libsource (lib "easyedapro") (part "RMCF0402FT649K"))
    )
    (comp (ref "R23")
      (value "10kΩ")
      (footprint "easyedapro:R0402")
      (fields (field (name "Manufacturer Part") "RC0402FR-0710KL") (field (name "Manufacturer") "YAGEO(国巨)"))
      (libsource (lib "easyedapro") (part "RC0402FR-0710KL"))
    )
    (comp (ref "R24")
      (value "30kΩ")
      (footprint "easyedapro:R0402")
      (fields (field (name "Manufacturer Part") "RC0402FR-0730KL") (field (name "Manufacturer") "YAGEO(国巨)"))
      (libsource (lib "easyedapro") (part "RC0402FR-0730KL"))
    )
    (comp (ref "U10")
      (value "TPS82130SILR")
      (footprint "easyedapro:USIP-8_L3.0-W2.8-P0.65-TL-EP")
      (fields (field (name "Manufacturer") "TI(德州仪器)"))
      (libsource (lib "easyedapro") (part "TPS82130SILR"))
    )
    (comp (ref "U11")
      (value "TPS82130SILR")
      (footprint "easyedapro:USIP-8_L3.0-W2.8-P0.65-TL-EP")
      (fields (field (name "Manufacturer") "TI(德州仪器)"))
      (libsource (lib "easyedapro") (part "TPS82130SILR"))
    )
    (comp (ref "U22")
      (value "330uF")
      (footprint "easyedapro:CAP-SMD_BD6.3-L6.6-W6.6-LS7.4-FD")
      (fields (field (name "Manufacturer Part") "RVT1A331M0607") (field (name "Manufacturer") "ROQANG(容强)"))
      (libsource (lib "easyedapro") (part "RVT1A331M0607_C7419412"))
    )
    (comp (ref "U23")
      (value "330uF")
      (footprint "easyedapro:CAP-SMD_BD6.3-L6.6-W6.6-LS7.4-FD")
      (fields (field (name "Manufacturer Part") "RVT1A331M0607") (field (name "Manufacturer") "ROQANG(容强)"))
      (libsource (lib "easyedapro") (part "RVT1A331M0607_C7419412"))
    )
    (comp (ref "C36")
      (value "4.7uF")
      (footprint "easyedapro:C0402")
      (fields
        (field (name "Manufacturer Part") "CL05A475MP5NRNC")
        (field (name "Manufacturer") "SAMSUNG(三星)")
      )
      (libsource (lib "easyedapro") (part "CL05A475MP5NRNC"))
    )
    (comp (ref "C37")
      (value "100nF")
      (footprint "easyedapro:C0201")
      (description "Capacitance:100nF Tolerance:±10% Tolerance:±10% Voltage Rating:16V Temperature Coefficient:X5R")
      (fields (field (name "Manufacturer Part") "0201X104K160NT") (field (name "Manufacturer") "FH(风华)"))
      (libsource (lib "easyedapro") (part "0201X104K160NT"))
    )
    (comp (ref "C38")
      (value "4.7uF")
      (footprint "easyedapro:C0402")
      (fields
        (field (name "Manufacturer Part") "CL05A475MP5NRNC")
        (field (name "Manufacturer") "SAMSUNG(三星)")
      )
      (libsource (lib "easyedapro") (part "CL05A475MP5NRNC"))
    )
    (comp (ref "R8")
      (value "2.2kΩ")
      (footprint "easyedapro:R0402")
      (description "Resistance:2.2kΩ Tolerance:±5% Tolerance:±5% Power(Watts):62.5mW")
      (fields (field (name "Manufacturer Part") "RMC04022.2K5%N") (field (name "Manufacturer") "Tyohm(幸亚电阻)"))
      (libsource (lib "easyedapro") (part "RMC04022.2K5%N"))
    )
    (comp (ref "R9")
      (value "2.2kΩ")
      (footprint "easyedapro:R0402")
      (description "Resistance:2.2kΩ Tolerance:±5% Tolerance:±5% Power(Watts):62.5mW")
      (fields (field (name "Manufacturer Part") "RMC04022.2K5%N") (field (name "Manufacturer") "Tyohm(幸亚电阻)"))
      (libsource (lib "easyedapro") (part "RMC04022.2K5%N"))
    )
    (comp (ref "R10")
      (value "47kΩ")
      (footprint "easyedapro:R0402")
      (fields (field (name "Manufacturer Part") "RC0402FR-0747KL") (field (name "Manufacturer") "YAGEO(国巨)"))
      (libsource (lib "easyedapro") (part "RC0402FR-0747KL"))
    )
    (comp (ref "R12")
      (value "47kΩ")
      (footprint "easyedapro:R0402")
      (fields (field (name "Manufacturer Part") "RC0402FR-0747KL") (field (name "Manufacturer") "YAGEO(国巨)"))
      (libsource (lib "easyedapro") (part "RC0402FR-0747KL"))
    )
    (comp (ref "R13")
      (value "47kΩ")
      (footprint "easyedapro:R0402")
      (fields (field (name "Manufacturer Part") "RC0402FR-0747KL") (field (name "Manufacturer") "YAGEO(国巨)"))
      (libsource (lib "easyedapro") (part "RC0402FR-0747KL"))
    )
    (comp (ref "R14")
      (value "47kΩ")
      (footprint "easyedapro:R0402")
      (fields (field (name "Manufacturer Part") "RC0402FR-0747KL") (field (name "Manufacturer") "YAGEO(国巨)"))
      (libsource (lib "easyedapro") (part "RC0402FR-0747KL"))
    )
    (comp (ref "R44")
      (value "22Ω")
      (footprint "easyedapro:R0402")
      (fields
        (field (name "Manufacturer Part") "0402WGF220JTCE")
        (field (name "Manufacturer") "UNI-ROYAL(厚声)")
      )
      (libsource (lib "easyedapro") (part "0402WGF220JTCE"))
    )
    (comp (ref "R45")
      (value "22Ω")
      (footprint "easyedapro:R0402")
      (fields
        (field (name "Manufacturer Part") "0402WGF220JTCE")
        (field (name "Manufacturer") "UNI-ROYAL(厚声)")
      )
      (libsource (lib "easyedapro") (part "0402WGF220JTCE"))
    )
    (comp (ref "tof5")
      (value "WAFER-SH1.0-4PLB")
      (footprint "easyedapro:CONN-SMD_4P-P1.00-C3029334")
      (fields (field (name "Manufacturer") "XUNPU(讯普)"))
      (libsource (lib "easyedapro") (part "WAFER-SH1.0-4PLB"))
    )
    (comp (ref "U18")
      (value "VL53L7CXV0GC/1")
      (footprint "easyedapro:LGA-16_L6.4-W3.0_VL53L5CXV0GC-1")
      (fields (field (name "Manufacturer") "ST(意法半导体)"))
      (libsource (lib "easyedapro") (part "VL53L7CXV0GC/1"))
    )
    (comp (ref "C42")
      (value "22uF")
      (footprint "easyedapro:C0805")
      (fields
        (field (name "Manufacturer Part") "CL21A226MAYNNNE")
        (field (name "Manufacturer") "SAMSUNG(三星)")
      )
      (libsource (lib "easyedapro") (part "CL21A226MAYNNNE"))
    )
    (comp (ref "C59")
      (value "330nF")
      (footprint "easyedapro:C1206")
      (fields
        (field (name "Manufacturer Part") "CC1206KRX7R9BB334")
        (field (name "Manufacturer") "YAGEO(国巨)")
      )
      (libsource (lib "easyedapro") (part "CC1206KRX7R9BB334"))
    )
    (comp (ref "C60")
      (value "330nF")
      (footprint "easyedapro:C1206")
      (fields
        (field (name "Manufacturer Part") "CC1206KRX7R9BB334")
        (field (name "Manufacturer") "YAGEO(国巨)")
      )
      (libsource (lib "easyedapro") (part "CC1206KRX7R9BB334"))
    )
    (comp (ref "C61")
      (value "330nF")
      (footprint "easyedapro:C1206")
      (fields
        (field (name "Manufacturer Part") "CC1206KRX7R9BB334")
        (field (name "Manufacturer") "YAGEO(国巨)")
      )
      (libsource (lib "easyedapro") (part "CC1206KRX7R9BB334"))
    )
    (comp (ref "C62")
      (value "330nF")
      (footprint "easyedapro:C1206")
      (fields
        (field (name "Manufacturer Part") "CC1206KRX7R9BB334")
        (field (name "Manufacturer") "YAGEO(国巨)")
      )
      (libsource (lib "easyedapro") (part "CC1206KRX7R9BB334"))
    )
    (comp (ref "C64")
      (value "22uF")
      (footprint "easyedapro:C0805")
      (fields
        (field (name "Manufacturer Part") "CL21A226MAYNNNE")
        (field (name "Manufacturer") "SAMSUNG(三星)")
      )
      (libsource (lib "easyedapro") (part "CL21A226MAYNNNE"))
    )
    (comp (ref "LED4")
      (value "SK9822-EC20")
      (footprint "easyedapro:LED-SMD_6P-L2.0-W2.0-P0.80-TL")
      (fields (field (name "Manufacturer") "欧思科光电"))
      (libsource (lib "easyedapro") (part "SK9822-EC20"))
    )
    (comp (ref "LED5")
      (value "SK9822-EC20")
      (footprint "easyedapro:LED-SMD_6P-L2.0-W2.0-P0.80-TL")
      (fields (field (name "Manufacturer") "欧思科光电"))
      (libsource (lib "easyedapro") (part "SK9822-EC20"))
    )
    (comp (ref "LED6")
      (value "SK9822-EC20")
      (footprint "easyedapro:LED-SMD_6P-L2.0-W2.0-P0.80-TL")
      (fields (field (name "Manufacturer") "欧思科光电"))
      (libsource (lib "easyedapro") (part "SK9822-EC20"))
    )
    (comp (ref "LED7")
      (value "SK9822-EC20")
      (footprint "easyedapro:LED-SMD_6P-L2.0-W2.0-P0.80-TL")
      (fields (field (name "Manufacturer") "欧思科光电"))
      (libsource (lib "easyedapro") (part "SK9822-EC20"))
    )
    (comp (ref "LED8")
      (value "SK9822-EC20")
      (footprint "easyedapro:LED-SMD_6P-L2.0-W2.0-P0.80-TL")
      (fields (field (name "Manufacturer") "欧思科光电"))
      (libsource (lib "easyedapro") (part "SK9822-EC20"))
    )
    (comp (ref "LED9")
      (value "SK9822-EC20")
      (footprint "easyedapro:LED-SMD_6P-L2.0-W2.0-P0.80-TL")
      (fields (field (name "Manufacturer") "欧思科光电"))
      (libsource (lib "easyedapro") (part "SK9822-EC20"))
    )
    (comp (ref "LED10")
      (value "SK9822-EC20")
      (footprint "easyedapro:LED-SMD_6P-L2.0-W2.0-P0.80-TL")
      (fields (field (name "Manufacturer") "欧思科光电"))
      (libsource (lib "easyedapro") (part "SK9822-EC20"))
    )
    (comp (ref "LED11")
      (value "SK9822-EC20")
      (footprint "easyedapro:LED-SMD_6P-L2.0-W2.0-P0.80-TL")
      (fields (field (name "Manufacturer") "欧思科光电"))
      (libsource (lib "easyedapro") (part "SK9822-EC20"))
    )
    (comp (ref "R21")
      (value "100Ω")
      (footprint "easyedapro:R0402")
      (fields
        (field (name "Manufacturer Part") "0402WGF1000TCE")
        (field (name "Manufacturer") "UNI-ROYAL(厚声)")
      )
      (libsource (lib "easyedapro") (part "0402WGF1000TCE"))
    )
    (comp (ref "R22")
      (value "100Ω")
      (footprint "easyedapro:R0402")
      (fields
        (field (name "Manufacturer Part") "0402WGF1000TCE")
        (field (name "Manufacturer") "UNI-ROYAL(厚声)")
      )
      (libsource (lib "easyedapro") (part "0402WGF1000TCE"))
    )
    (comp (ref "U20")
      (value "AMS1117-5.0")
      (footprint "easyedapro:SOT-223_L6.5-W3.5-P2.30-LS7.0-BR")
      (fields (field (name "Manufacturer") "AMS"))
      (libsource (lib "easyedapro") (part "AMS1117-5.0"))
    )
    (comp (ref "D8")
      (value "RCLAMP0521P-N")
      (footprint "easyedapro:X1-DFN1006-2_L1.0-W0.6-P0.65-BI")
      (fields (field (name "Manufacturer") "BORN(伯恩半导体)"))
      (libsource (lib "easyedapro") (part "RCLAMP0521P-N"))
    )
    (comp (ref "D9")
      (value "RCLAMP0521P-N")
      (footprint "easyedapro:X1-DFN1006-2_L1.0-W0.6-P0.65-BI")
      (fields (field (name "Manufacturer") "BORN(伯恩半导体)"))
      (libsource (lib "easyedapro") (part "RCLAMP0521P-N"))
    )
    (comp (ref "D10")
      (value "RCLAMP0521P-N")
      (footprint "easyedapro:X1-DFN1006-2_L1.0-W0.6-P0.65-BI")
      (fields (field (name "Manufacturer") "BORN(伯恩半导体)"))
      (libsource (lib "easyedapro") (part "RCLAMP0521P-N"))
    )
    (comp (ref "D11")
      (value "RCLAMP0521P-N")
      (footprint "easyedapro:X1-DFN1006-2_L1.0-W0.6-P0.65-BI")
      (fields (field (name "Manufacturer") "BORN(伯恩半导体)"))
      (libsource (lib "easyedapro") (part "RCLAMP0521P-N"))
    )
    (comp (ref "D12")
      (value "RCLAMP0521P-N")
      (footprint "easyedapro:X1-DFN1006-2_L1.0-W0.6-P0.65-BI")
      (fields (field (name "Manufacturer") "BORN(伯恩半导体)"))
      (libsource (lib "easyedapro") (part "RCLAMP0521P-N"))
    )
    (comp (ref "D13")
      (value "RCLAMP0521P-N")
      (footprint "easyedapro:X1-DFN1006-2_L1.0-W0.6-P0.65-BI")
      (fields (field (name "Manufacturer") "BORN(伯恩半导体)"))
      (libsource (lib "easyedapro") (part "RCLAMP0521P-N"))
    )
    (comp (ref "R25")
      (value "470Ω")
      (footprint "easyedapro:R0402")
      (fields
        (field (name "Manufacturer Part") "0402WGF4700TCE")
        (field (name "Manufacturer") "UNI-ROYAL(厚声)")
      )
      (libsource (lib "easyedapro") (part "0402WGF4700TCE"))
    )
    (comp (ref "R26")
      (value "470Ω")
      (footprint "easyedapro:R0402")
      (fields
        (field (name "Manufacturer Part") "0402WGF4700TCE")
        (field (name "Manufacturer") "UNI-ROYAL(厚声)")
      )
      (libsource (lib "easyedapro") (part "0402WGF4700TCE"))
    )
    (comp (ref "R27")
      (value "470Ω")
      (footprint "easyedapro:R0402")
      (fields
        (field (name "Manufacturer Part") "0402WGF4700TCE")
        (field (name "Manufacturer") "UNI-ROYAL(厚声)")
      )
      (libsource (lib "easyedapro") (part "0402WGF4700TCE"))
    )
    (comp (ref "R28")
      (value "470Ω")
      (footprint "easyedapro:R0402")
      (fields
        (field (name "Manufacturer Part") "0402WGF4700TCE")
        (field (name "Manufacturer") "UNI-ROYAL(厚声)")
      )
      (libsource (lib "easyedapro") (part "0402WGF4700TCE"))
    )
    (comp (ref "R29")
      (value "470Ω")
      (footprint "easyedapro:R0402")
      (fields
        (field (name "Manufacturer Part") "0402WGF4700TCE")
        (field (name "Manufacturer") "UNI-ROYAL(厚声)")
      )
      (libsource (lib "easyedapro") (part "0402WGF4700TCE"))
    )
    (comp (ref "R30")
      (value "470Ω")
      (footprint "easyedapro:R0402")
      (fields
        (field (name "Manufacturer Part") "0402WGF4700TCE")
        (field (name "Manufacturer") "UNI-ROYAL(厚声)")
      )
      (libsource (lib "easyedapro") (part "0402WGF4700TCE"))
    )
    (comp (ref "SERVO2")
      (value "HX PZ2.54-3x6P ZZ")
      (footprint "easyedapro:CONN-TH_HX-PZ2.54-3X6P-ZZ")
      (fields (field (name "Manufacturer") "hanxia(韩下)"))
      (libsource (lib "easyedapro") (part "HX PZ2.54-3X6P ZZ"))
    )
    (comp (ref "D14")
      (value "RCLAMP0521P-N")
      (footprint "easyedapro:X1-DFN1006-2_L1.0-W0.6-P0.65-BI")
      (fields (field (name "Manufacturer") "BORN(伯恩半导体)"))
      (libsource (lib "easyedapro") (part "RCLAMP0521P-N"))
    )
    (comp (ref "D15")
      (value "RCLAMP0521P-N")
      (footprint "easyedapro:X1-DFN1006-2_L1.0-W0.6-P0.65-BI")
      (fields (field (name "Manufacturer") "BORN(伯恩半导体)"))
      (libsource (lib "easyedapro") (part "RCLAMP0521P-N"))
    )
    (comp (ref "H1")
      (value "PZ254V-11-03P")
      (footprint "easyedapro:HDR-TH_3P-P2.54-V-M")
      (fields (field (name "Manufacturer") "XFCN(兴飞)"))
      (libsource (lib "easyedapro") (part "PZ254V-11-03P_C2937625"))
    )
    (comp (ref "R52")
      (value "220Ω")
      (footprint "easyedapro:R0603")
      (fields
        (field (name "Manufacturer Part") "0603WAF2200T5E")
        (field (name "Manufacturer") "UNI-ROYAL(厚声)")
      )
      (libsource (lib "easyedapro") (part "0603WAF2200T5E"))
    )
    (comp (ref "R53")
      (value "220Ω")
      (footprint "easyedapro:R0603")
      (fields
        (field (name "Manufacturer Part") "0603WAF2200T5E")
        (field (name "Manufacturer") "UNI-ROYAL(厚声)")
      )
      (libsource (lib "easyedapro") (part "0603WAF2200T5E"))
    )
    (comp (ref "U6")
      (value "PM254-1-16-Z-8.5")
      (footprint "easyedapro:HDR-TH_16P-P2.54-V-F-A")
      (fields (field (name "Manufacturer") "HCTL(华灿天禄)"))
      (libsource (lib "easyedapro") (part "PM254-1-16-Z-8.5"))
    )
    (comp (ref "U7")
      (value "PM254-1-16-Z-8.5")
      (footprint "easyedapro:HDR-TH_16P-P2.54-V-F-A")
      (fields (field (name "Manufacturer") "HCTL(华灿天禄)"))
      (libsource (lib "easyedapro") (part "PM254-1-16-Z-8.5"))
    )
    (comp (ref "D16")
      (value "RCLAMP0521P-N")
      (footprint "easyedapro:X1-DFN1006-2_L1.0-W0.6-P0.65-BI")
      (fields (field (name "Manufacturer") "BORN(伯恩半导体)"))
      (libsource (lib "easyedapro") (part "RCLAMP0521P-N"))
    )
    (comp (ref "D17")
      (value "RCLAMP0521P-N")
      (footprint "easyedapro:X1-DFN1006-2_L1.0-W0.6-P0.65-BI")
      (fields (field (name "Manufacturer") "BORN(伯恩半导体)"))
      (libsource (lib "easyedapro") (part "RCLAMP0521P-N"))
    )
    (comp (ref "H2")
      (value "FTSH-107-01-F-DV-K")
      (footprint "easyedapro:CONN-SMD_14P-P1.27_FTSH-107-01-F-DV-K-P-TR")
      (fields (field (name "Manufacturer") "SAMTEC"))
      (libsource (lib "easyedapro") (part "FTSH-107-01-F-DV-K"))
    )
    (comp (ref "R60")
      (value "33Ω")
      (footprint "easyedapro:R0402")
      (fields
        (field (name "Manufacturer Part") "0402WGF330JTCE")
        (field (name "Manufacturer") "UNI-ROYAL(厚声)")
      )
      (libsource (lib "easyedapro") (part "0402WGF330JTCE"))
    )
    (comp (ref "R61")
      (value "33Ω")
      (footprint "easyedapro:R0402")
      (fields
        (field (name "Manufacturer Part") "0402WGF330JTCE")
        (field (name "Manufacturer") "UNI-ROYAL(厚声)")
      )
      (libsource (lib "easyedapro") (part "0402WGF330JTCE"))
    )
    (comp (ref "R62")
      (value "33Ω")
      (footprint "easyedapro:R0402")
      (fields
        (field (name "Manufacturer Part") "0402WGF330JTCE")
        (field (name "Manufacturer") "UNI-ROYAL(厚声)")
      )
      (libsource (lib "easyedapro") (part "0402WGF330JTCE"))
    )
    (comp (ref "R63")
      (value "33Ω")
      (footprint "easyedapro:R0402")
      (fields
        (field (name "Manufacturer Part") "0402WGF330JTCE")
        (field (name "Manufacturer") "UNI-ROYAL(厚声)")
      )
      (libsource (lib "easyedapro") (part "0402WGF330JTCE"))
    )
    (comp (ref "R64")
      (value "33Ω")
      (footprint "easyedapro:R0402")
      (fields
        (field (name "Manufacturer Part") "0402WGF330JTCE")
        (field (name "Manufacturer") "UNI-ROYAL(厚声)")
      )
      (libsource (lib "easyedapro") (part "0402WGF330JTCE"))
    )
    (comp (ref "R67")
      (value "33Ω")
      (footprint "easyedapro:R0402")
      (fields
        (field (name "Manufacturer Part") "0402WGF330JTCE")
        (field (name "Manufacturer") "UNI-ROYAL(厚声)")
      )
      (libsource (lib "easyedapro") (part "0402WGF330JTCE"))
    )
    (comp (ref "R68")
      (value "33Ω")
      (footprint "easyedapro:R0402")
      (fields
        (field (name "Manufacturer Part") "0402WGF330JTCE")
        (field (name "Manufacturer") "UNI-ROYAL(厚声)")
      )
      (libsource (lib "easyedapro") (part "0402WGF330JTCE"))
    )
    (comp (ref "adc6")
      (value "WAFER-SH1.0-4PLB")
      (footprint "easyedapro:CONN-SMD_4P-P1.00-C3029334")
      (fields (field (name "Manufacturer") "XUNPU(讯普)"))
      (libsource (lib "easyedapro") (part "WAFER-SH1.0-4PLB"))
    )
    (comp (ref "ADC24")
      (value "WAFER-SH1.0-6PLB")
      (footprint "easyedapro:CONN-SMD_6P-P1.00_1734595-6")
      (fields (field (name "Manufacturer") "XUNPU(讯普)"))
      (libsource (lib "easyedapro") (part "WAFER-SH1.0-6PLB"))
    )
    (comp (ref "C53")
      (value "100nF")
      (footprint "easyedapro:C0201")
      (description "Capacitance:100nF Tolerance:±10% Tolerance:±10% Voltage Rating:16V Temperature Coefficient:X5R")
      (fields (field (name "Manufacturer Part") "0201X104K160NT") (field (name "Manufacturer") "FH(风华)"))
      (libsource (lib "easyedapro") (part "0201X104K160NT"))
    )
    (comp (ref "C54")
      (value "100nF")
      (footprint "easyedapro:C0201")
      (description "Capacitance:100nF Tolerance:±10% Tolerance:±10% Voltage Rating:16V Temperature Coefficient:X5R")
      (fields (field (name "Manufacturer Part") "0201X104K160NT") (field (name "Manufacturer") "FH(风华)"))
      (libsource (lib "easyedapro") (part "0201X104K160NT"))
    )
    (comp (ref "C55")
      (value "100nF")
      (footprint "easyedapro:C0201")
      (description "Capacitance:100nF Tolerance:±10% Tolerance:±10% Voltage Rating:16V Temperature Coefficient:X5R")
      (fields (field (name "Manufacturer Part") "0201X104K160NT") (field (name "Manufacturer") "FH(风华)"))
      (libsource (lib "easyedapro") (part "0201X104K160NT"))
    )
    (comp (ref "C56")
      (value "100nF")
      (footprint "easyedapro:C0201")
      (description "Capacitance:100nF Tolerance:±10% Tolerance:±10% Voltage Rating:16V Temperature Coefficient:X5R")
      (fields (field (name "Manufacturer Part") "0201X104K160NT") (field (name "Manufacturer") "FH(风华)"))
      (libsource (lib "easyedapro") (part "0201X104K160NT"))
    )
    (comp (ref "C57")
      (value "100nF")
      (footprint "easyedapro:C0201")
      (description "Capacitance:100nF Tolerance:±10% Tolerance:±10% Voltage Rating:16V Temperature Coefficient:X5R")
      (fields (field (name "Manufacturer Part") "0201X104K160NT") (field (name "Manufacturer") "FH(风华)"))
      (libsource (lib "easyedapro") (part "0201X104K160NT"))
    )
    (comp (ref "C58")
      (value "100nF")
      (footprint "easyedapro:C0201")
      (description "Capacitance:100nF Tolerance:±10% Tolerance:±10% Voltage Rating:16V Temperature Coefficient:X5R")
      (fields (field (name "Manufacturer Part") "0201X104K160NT") (field (name "Manufacturer") "FH(风华)"))
      (libsource (lib "easyedapro") (part "0201X104K160NT"))
    )
    (comp (ref "R46")
      (value "15kΩ")
      (footprint "easyedapro:R0402")
      (fields (field (name "Manufacturer Part") "RC0402FR-0715KL") (field (name "Manufacturer") "YAGEO(国巨)"))
      (libsource (lib "easyedapro") (part "RC0402FR-0715KL"))
    )
    (comp (ref "R47")
      (value "15kΩ")
      (footprint "easyedapro:R0402")
      (fields (field (name "Manufacturer Part") "RC0402FR-0715KL") (field (name "Manufacturer") "YAGEO(国巨)"))
      (libsource (lib "easyedapro") (part "RC0402FR-0715KL"))
    )
    (comp (ref "R48")
      (value "15kΩ")
      (footprint "easyedapro:R0402")
      (fields (field (name "Manufacturer Part") "RC0402FR-0715KL") (field (name "Manufacturer") "YAGEO(国巨)"))
      (libsource (lib "easyedapro") (part "RC0402FR-0715KL"))
    )
    (comp (ref "R49")
      (value "15kΩ")
      (footprint "easyedapro:R0402")
      (fields (field (name "Manufacturer Part") "RC0402FR-0715KL") (field (name "Manufacturer") "YAGEO(国巨)"))
      (libsource (lib "easyedapro") (part "RC0402FR-0715KL"))
    )
    (comp (ref "R50")
      (value "15kΩ")
      (footprint "easyedapro:R0402")
      (fields (field (name "Manufacturer Part") "RC0402FR-0715KL") (field (name "Manufacturer") "YAGEO(国巨)"))
      (libsource (lib "easyedapro") (part "RC0402FR-0715KL"))
    )
    (comp (ref "R51")
      (value "15kΩ")
      (footprint "easyedapro:R0402")
      (fields (field (name "Manufacturer Part") "RC0402FR-0715KL") (field (name "Manufacturer") "YAGEO(国巨)"))
      (libsource (lib "easyedapro") (part "RC0402FR-0715KL"))
    )
  )
  (nets
    (net (code "1") (name "+3.3V") (class "Default")
      (node (ref "ADC24") (pin "1") (pinfunction "1_1") (pintype "unspecified"))
      (node (ref "BOOT0") (pin "1") (pinfunction "1_1") (pintype "unspecified"))
      (node (ref "BOOT0") (pin "2") (pinfunction "2_2") (pintype "unspecified"))
      (node (ref "C15") (pin "2") (pinfunction "2_2") (pintype "input"))
      (node (ref "C16") (pin "2") (pinfunction "2_2") (pintype "unspecified"))
      (node (ref "C17") (pin "2") (pinfunction "2_2") (pintype "unspecified"))
      (node (ref "C19") (pin "2") (pinfunction "2_2") (pintype "unspecified"))
      (node (ref "C20") (pin "2") (pinfunction "2_2") (pintype "unspecified"))
      (node (ref "C21") (pin "2") (pinfunction "2_2") (pintype "unspecified"))
      (node (ref "C22") (pin "2") (pinfunction "2_2") (pintype "unspecified"))
      (node (ref "C24") (pin "2") (pinfunction "2_2") (pintype "unspecified"))
      (node (ref "C27") (pin "2") (pinfunction "2_2") (pintype "unspecified"))
      (node (ref "C36") (pin "2") (pinfunction "2_2") (pintype "input"))
      (node (ref "C37") (pin "2") (pinfunction "2_2") (pintype "unspecified"))
      (node (ref "C38") (pin "2") (pinfunction "2_2") (pintype "input"))
      (node (ref "C67") (pin "2") (pinfunction "2_2") (pintype "unspecified"))
      (node (ref "D5") (pin "2") (pinfunction "2_2") (pintype "unspecified"))
      (node (ref "D6") (pin "2") (pinfunction "2_2") (pintype "unspecified"))
      (node (ref "H2") (pin "3") (pinfunction "3_3") (pintype "unspecified"))
      (node (ref "R1") (pin "2") (pinfunction "2_2") (pintype "input"))
      (node (ref "R10") (pin "2") (pinfunction "2_2") (pintype "input"))
      (node (ref "R11") (pin "2") (pinfunction "2_2") (pintype "input"))
      (node (ref "R13") (pin "2") (pinfunction "2_2") (pintype "input"))
      (node (ref "R14") (pin "2") (pinfunction "2_2") (pintype "input"))
      (node (ref "R3") (pin "2") (pinfunction "2_2") (pintype "unspecified"))
      (node (ref "R7") (pin "2") (pinfunction "2_2") (pintype "input"))
      (node (ref "R8") (pin "2") (pinfunction "2_2") (pintype "input"))
      (node (ref "R9") (pin "2") (pinfunction "2_2") (pintype "input"))
      (node (ref "U10") (pin "4") (pinfunction "VOUT_4") (pintype "unspecified"))
      (node (ref "U10") (pin "5") (pinfunction "VOUT_5") (pintype "unspecified"))
      (node (ref "U18") (pin "A4") (pinfunction "IOVDD_A4") (pintype "unspecified"))
      (node (ref "U18") (pin "B1") (pinfunction "AVDD_B1") (pintype "unspecified"))
      (node (ref "U18") (pin "B7") (pinfunction "AVDD_B7") (pintype "unspecified"))
      (node (ref "U24") (pin "5") (pinfunction "5_5") (pintype "unspecified"))
      (node (ref "U25") (pin "5") (pinfunction "5_5") (pintype "unspecified"))
      (node (ref "U6") (pin "1") (pinfunction "1_1") (pintype "unspecified"))
      (node (ref "U9") (pin "1") (pinfunction "VBAT_1") (pintype "unspecified"))
      (node (ref "U9") (pin "13") (pinfunction "VDDA_13") (pintype "unspecified"))
      (node (ref "U9") (pin "19") (pinfunction "VDD_19") (pintype "unspecified"))
      (node (ref "U9") (pin "32") (pinfunction "VDD_32") (pintype "unspecified"))
      (node (ref "U9") (pin "48") (pinfunction "VDD_48") (pintype "unspecified"))
      (node (ref "U9") (pin "64") (pinfunction "VDD_64") (pintype "unspecified"))
      (node (ref "adc6") (pin "4") (pinfunction "4_4") (pintype "unspecified"))
      (node (ref "tof5") (pin "4") (pinfunction "4_4") (pintype "unspecified"))
    )
    (net (code "2") (name "+5.0V") (class "Default")
      (node (ref "C42") (pin "2") (pinfunction "2_2") (pintype "unspecified"))
      (node (ref "C59") (pin "2") (pinfunction "2_2") (pintype "input"))
      (node (ref "C60") (pin "2") (pinfunction "2_2") (pintype "input"))
      (node (ref "C61") (pin "2") (pinfunction "2_2") (pintype "input"))
      (node (ref "C62") (pin "2") (pinfunction "2_2") (pintype "input"))
      (node (ref "LED10") (pin "5") (pinfunction "VDD_5") (pintype "unspecified"))
      (node (ref "LED11") (pin "5") (pinfunction "VDD_5") (pintype "unspecified"))
      (node (ref "LED4") (pin "5") (pinfunction "VDD_5") (pintype "unspecified"))
      (node (ref "LED5") (pin "5") (pinfunction "VDD_5") (pintype "unspecified"))
      (node (ref "LED6") (pin "5") (pinfunction "VDD_5") (pintype "unspecified"))
      (node (ref "LED7") (pin "5") (pinfunction "VDD_5") (pintype "unspecified"))
      (node (ref "LED8") (pin "5") (pinfunction "VDD_5") (pintype "unspecified"))
      (node (ref "LED9") (pin "5") (pinfunction "VDD_5") (pintype "unspecified"))
      (node (ref "U20") (pin "2") (pinfunction "VOUT_2") (pintype "unspecified"))
      (node (ref "U20") (pin "4") (pinfunction "VOUT_4") (pintype "unspecified"))
    )
    (net (code "3") (name "+6.0V") (class "Default")
      (node (ref "C30") (pin "2") (pinfunction "2_2") (pintype "unspecified"))
      (node (ref "C64") (pin "2") (pinfunction "2_2") (pintype "unspecified"))
      (node (ref "R4") (pin "2") (pinfunction "2_2") (pintype "input"))
      (node (ref "R6") (pin "2") (pinfunction "2_2") (pintype "unspecified"))
      (node (ref "SERVO2") (pin "10") (pinfunction "10_10") (pintype "unspecified"))
      (node (ref "SERVO2") (pin "11") (pinfunction "11_11") (pintype "unspecified"))
      (node (ref "SERVO2") (pin "12") (pinfunction "12_12") (pintype "unspecified"))
      (node (ref "SERVO2") (pin "7") (pinfunction "7_7") (pintype "unspecified"))
      (node (ref "SERVO2") (pin "8") (pinfunction "8_8") (pintype "unspecified"))
      (node (ref "SERVO2") (pin "9") (pinfunction "9_9") (pintype "unspecified"))
      (node (ref "U11") (pin "4") (pinfunction "VOUT_4") (pintype "unspecified"))
      (node (ref "U11") (pin "5") (pinfunction "VOUT_5") (pintype "unspecified"))
      (node (ref "U20") (pin "3") (pinfunction "VIN_3") (pintype "unspecified"))
      (node (ref "U22") (pin "1") (pinfunction "1_1") (pintype "input"))
    )
    (net (code "4") (name "ADC4") (class "Default")
      (node (ref "C56") (pin "2") (pinfunction "2_2") (pintype "unspecified"))
      (node (ref "R49") (pin "1") (pinfunction "1_1") (pintype "input"))
      (node (ref "U9") (pin "24") (pinfunction "PC4_24") (pintype "unspecified"))
    )
    (net (code "5") (name "ADC8") (class "Default")
      (node (ref "C57") (pin "2") (pinfunction "2_2") (pintype "unspecified"))
      (node (ref "R50") (pin "1") (pinfunction "1_1") (pintype "input"))
      (node (ref "U9") (pin "25") (pinfunction "PC5_25") (pintype "unspecified"))
    )
    (net (code "6") (name "ADC9") (class "Default")
      (node (ref "C58") (pin "2") (pinfunction "2_2") (pintype "unspecified"))
      (node (ref "R51") (pin "1") (pinfunction "1_1") (pintype "input"))
      (node (ref "U9") (pin "26") (pinfunction "PB0_26") (pintype "unspecified"))
    )
    (net (code "7") (name "ADC10") (class "Default")
      (node (ref "C53") (pin "2") (pinfunction "2_2") (pintype "unspecified"))
      (node (ref "R46") (pin "1") (pinfunction "1_1") (pintype "input"))
      (node (ref "U9") (pin "8") (pinfunction "PC0_8") (pintype "unspecified"))
    )
    (net (code "8") (name "ADC11") (class "Default")
      (node (ref "C54") (pin "2") (pinfunction "2_2") (pintype "unspecified"))
      (node (ref "R47") (pin "1") (pinfunction "1_1") (pintype "input"))
      (node (ref "U9") (pin "9") (pinfunction "PC1_9") (pintype "unspecified"))
    )
    (net (code "9") (name "ADC13") (class "Default")
      (node (ref "C55") (pin "2") (pinfunction "2_2") (pintype "unspecified"))
      (node (ref "R48") (pin "1") (pinfunction "1_1") (pintype "input"))
      (node (ref "U9") (pin "11") (pinfunction "PC3_11") (pintype "unspecified"))
    )
    (net (code "10") (name "BOOT0") (class "Default")
      (node (ref "BOOT0") (pin "3") (pinfunction "3_3") (pintype "unspecified"))
      (node (ref "BOOT0") (pin "4") (pinfunction "4_4") (pintype "unspecified"))
      (node (ref "R31") (pin "1") (pinfunction "1_1") (pintype "input"))
      (node (ref "U9") (pin "60") (pinfunction "BOOT0_60") (pintype "unspecified"))
    )
    (net (code "11") (name "ENCODER1_1") (class "Default")
      (node (ref "D3") (pin "2") (pinfunction "2_2") (pintype "unspecified"))
      (node (ref "R33") (pin "1") (pinfunction "1_1") (pintype "input"))
      (node (ref "U24") (pin "4") (pinfunction "4_4") (pintype "unspecified"))
    )
    (net (code "12") (name "ENCODER1_2") (class "Default")
      (node (ref "D4") (pin "2") (pinfunction "2_2") (pintype "unspecified"))
      (node (ref "R32") (pin "1") (pinfunction "1_1") (pintype "input"))
      (node (ref "U24") (pin "3") (pinfunction "3_3") (pintype "unspecified"))
    )
    (net (code "13") (name "ENCODER2_1") (class "Default")
      (node (ref "D1") (pin "2") (pinfunction "2_2") (pintype "unspecified"))
      (node (ref "R36") (pin "2") (pinfunction "2_2") (pintype "input"))
      (node (ref "U25") (pin "4") (pinfunction "4_4") (pintype "unspecified"))
    )
    (net (code "14") (name "ENCODER2_2") (class "Default")
      (node (ref "D2") (pin "2") (pinfunction "2_2") (pintype "unspecified"))
      (node (ref "R35") (pin "2") (pinfunction "2_2") (pintype "input"))
      (node (ref "U25") (pin "3") (pinfunction "3_3") (pintype "unspecified"))
    )
    (net (code "15") (name "GND") (class "Default")
      (node (ref "ADC24") (pin "6") (pinfunction "6_6") (pintype "unspecified"))
      (node (ref "ADC24") (pin "7") (pinfunction "7_7") (pintype "unspecified"))
      (node (ref "ADC24") (pin "8") (pinfunction "8_8") (pintype "unspecified"))
      (node (ref "BAT3") (pin "2") (pinfunction "2_2") (pintype "unspecified"))
      (node (ref "C15") (pin "1") (pinfunction "1_1") (pintype "input"))
      (node (ref "C16") (pin "1") (pinfunction "1_1") (pintype "unspecified"))
      (node (ref "C17") (pin "1") (pinfunction "1_1") (pintype "unspecified"))
      (node (ref "C19") (pin "1") (pinfunction "1_1") (pintype "unspecified"))
      (node (ref "C2") (pin "2") (pinfunction "2_2") (pintype "unspecified"))
      (node (ref "C20") (pin "1") (pinfunction "1_1") (pintype "unspecified"))
      (node (ref "C21") (pin "1") (pinfunction "1_1") (pintype "unspecified"))
      (node (ref "C22") (pin "1") (pinfunction "1_1") (pintype "unspecified"))
      (node (ref "C24") (pin "1") (pinfunction "1_1") (pintype "unspecified"))
      (node (ref "C25") (pin "1") (pinfunction "1_1") (pintype "unspecified"))
      (node (ref "C26") (pin "1") (pinfunction "1_1") (pintype "unspecified"))
      (node (ref "C27") (pin "1") (pinfunction "1_1") (pintype "unspecified"))
      (node (ref "C28") (pin "1") (pinfunction "1_1") (pintype "unspecified"))
      (node (ref "C29") (pin "1") (pinfunction "1_1") (pintype "unspecified"))
      (node (ref "C30") (pin "1") (pinfunction "1_1") (pintype "unspecified"))
      (node (ref "C32") (pin "1") (pinfunction "1_1") (pintype "unspecified"))
      (node (ref "C33") (pin "1") (pinfunction "1_1") (pintype "unspecified"))
      (node (ref "C34") (pin "1") (pinfunction "1_1") (pintype "unspecified"))
      (node (ref "C36") (pin "1") (pinfunction "1_1") (pintype "input"))
      (node (ref "C37") (pin "1") (pinfunction "1_1") (pintype "unspecified"))
      (node (ref "C38") (pin "1") (pinfunction "1_1") (pintype "input"))
      (node (ref "C42") (pin "1") (pinfunction "1_1") (pintype "unspecified"))
      (node (ref "C5") (pin "2") (pinfunction "2_2") (pintype "unspecified"))
      (node (ref "C51") (pin "1") (pinfunction "1_1") (pintype "unspecified"))
      (node (ref "C52") (pin "1") (pinfunction "1_1") (pintype "unspecified"))
      (node (ref "C53") (pin "1") (pinfunction "1_1") (pintype "unspecified"))
      (node (ref "C54") (pin "1") (pinfunction "1_1") (pintype "unspecified"))
      (node (ref "C55") (pin "1") (pinfunction "1_1") (pintype "unspecified"))
      (node (ref "C56") (pin "1") (pinfunction "1_1") (pintype "unspecified"))
      (node (ref "C57") (pin "1") (pinfunction "1_1") (pintype "unspecified"))
      (node (ref "C58") (pin "1") (pinfunction "1_1") (pintype "unspecified"))
      (node (ref "C59") (pin "1") (pinfunction "1_1") (pintype "input"))
      (node (ref "C60") (pin "1") (pinfunction "1_1") (pintype "input"))
      (node (ref "C61") (pin "1") (pinfunction "1_1") (pintype "input"))
      (node (ref "C62") (pin "1") (pinfunction "1_1") (pintype "input"))
      (node (ref "C63") (pin "1") (pinfunction "1_1") (pintype "unspecified"))
      (node (ref "C64") (pin "1") (pinfunction "1_1") (pintype "unspecified"))
      (node (ref "C67") (pin "1") (pinfunction "1_1") (pintype "unspecified"))
      (node (ref "D1") (pin "1") (pinfunction "1_1") (pintype "unspecified"))
      (node (ref "D10") (pin "1") (pinfunction "1_1") (pintype "unspecified"))
      (node (ref "D11") (pin "1") (pinfunction "1_1") (pintype "unspecified"))
      (node (ref "D12") (pin "1") (pinfunction "1_1") (pintype "unspecified"))
      (node (ref "D13") (pin "1") (pinfunction "1_1") (pintype "unspecified"))
      (node (ref "D14") (pin "1") (pinfunction "1_1") (pintype "unspecified"))
      (node (ref "D15") (pin "1") (pinfunction "1_1") (pintype "unspecified"))
      (node (ref "D16") (pin "1") (pinfunction "1_1") (pintype "unspecified"))
      (node (ref "D17") (pin "1") (pinfunction "1_1") (pintype "unspecified"))
      (node (ref "D2") (pin "1") (pinfunction "1_1") (pintype "unspecified"))
      (node (ref "D3") (pin "1") (pinfunction "1_1") (pintype "unspecified"))
      (node (ref "D4") (pin "1") (pinfunction "1_1") (pintype "unspecified"))
      (node (ref "D5") (pin "1") (pinfunction "1_1") (pintype "unspecified"))
      (node (ref "D6") (pin "1") (pinfunction "1_1") (pintype "unspecified"))
      (node (ref "D7") (pin "1") (pinfunction "1_1") (pintype "unspecified"))
      (node (ref "D8") (pin "1") (pinfunction "1_1") (pintype "unspecified"))
      (node (ref "D9") (pin "1") (pinfunction "1_1") (pintype "unspecified"))
      (node (ref "H1") (pin "3") (pinfunction "3_3") (pintype "unspecified"))
      (node (ref "H2") (pin "11") (pinfunction "11_11") (pintype "unspecified"))
      (node (ref "H2") (pin "5") (pinfunction "5_5") (pintype "unspecified"))
      (node (ref "H2") (pin "7") (pinfunction "7_7") (pintype "unspecified"))
      (node (ref "LED10") (pin "2") (pinfunction "GND_2") (pintype "unspecified"))
      (node (ref "LED11") (pin "2") (pinfunction "GND_2") (pintype "unspecified"))
      (node (ref "LED4") (pin "2") (pinfunction "GND_2") (pintype "unspecified"))
      (node (ref "LED5") (pin "2") (pinfunction "GND_2") (pintype "unspecified"))
      (node (ref "LED6") (pin "2") (pinfunction "GND_2") (pintype "unspecified"))
      (node (ref "LED7") (pin "2") (pinfunction "GND_2") (pintype "unspecified"))
      (node (ref "LED8") (pin "2") (pinfunction "GND_2") (pintype "unspecified"))
      (node (ref "LED9") (pin "2") (pinfunction "GND_2") (pintype "unspecified"))
      (node (ref "NRST1") (pin "3") (pinfunction "3_3") (pintype "unspecified"))
      (node (ref "NRST1") (pin "4") (pinfunction "4_4") (pintype "unspecified"))
      (node (ref "R12") (pin "1") (pinfunction "1_1") (pintype "input"))
      (node (ref "R2") (pin "1") (pinfunction "1_1") (pintype "input"))
      (node (ref "R23") (pin "1") (pinfunction "1_1") (pintype "input"))
      (node (ref "R31") (pin "2") (pinfunction "2_2") (pintype "input"))
      (node (ref "R5") (pin "1") (pinfunction "1_1") (pintype "input"))
      (node (ref "SERVO2") (pin "13") (pinfunction "13_13") (pintype "unspecified"))
      (node (ref "SERVO2") (pin "14") (pinfunction "14_14") (pintype "unspecified"))
      (node (ref "SERVO2") (pin "15") (pinfunction "15_15") (pintype "unspecified"))
      (node (ref "SERVO2") (pin "16") (pinfunction "16_16") (pintype "unspecified"))
      (node (ref "SERVO2") (pin "17") (pinfunction "17_17") (pintype "unspecified"))
      (node (ref "SERVO2") (pin "18") (pinfunction "18_18") (pintype "unspecified"))
      (node (ref "U10") (pin "3") (pinfunction "GND_3") (pintype "unspecified"))
      (node (ref "U10") (pin "9") (pinfunction "EP_9") (pintype "unspecified"))
      (node (ref "U11") (pin "3") (pinfunction "GND_3") (pintype "unspecified"))
      (node (ref "U11") (pin "9") (pinfunction "EP_9") (pintype "unspecified"))
      (node (ref "U16") (pin "1") (pinfunction "1_1") (pintype "unspecified"))
      (node (ref "U17") (pin "1") (pinfunction "1_1") (pintype "unspecified"))
      (node (ref "U18") (pin "A2") (pinfunction "RSVD4_A2") (pintype "unspecified"))
      (node (ref "U18") (pin "A6") (pinfunction "RSVD1_A6") (pintype "unspecified"))
      (node (ref "U18") (pin "A7") (pinfunction "RSVD2_A7") (pintype "unspecified"))
      (node (ref "U18") (pin "B4") (pinfunction "THERMALPAD_B4") (pintype "unspecified"))
      (node (ref "U18") (pin "C1") (pinfunction "GND_C1") (pintype "unspecified"))
      (node (ref "U18") (pin "C6") (pinfunction "RSVD3_C6") (pintype "unspecified"))
      (node (ref "U18") (pin "C7") (pinfunction "GND_C7") (pintype "unspecified"))
      (node (ref "U2") (pin "13") (pinfunction "GND_13") (pintype "unspecified"))
      (node (ref "U2") (pin "17") (pinfunction "GND_17") (pintype "unspecified"))
      (node (ref "U20") (pin "1") (pinfunction "GND_1") (pintype "unspecified"))
      (node (ref "U22") (pin "2") (pinfunction "2_2") (pintype "input"))
      (node (ref "U23") (pin "2") (pinfunction "2_2") (pintype "input"))
      (node (ref "U24") (pin "1") (pinfunction "1_1") (pintype "unspecified"))
      (node (ref "U24") (pin "7") (pinfunction "7_7") (pintype "unspecified"))
      (node (ref "U24") (pin "8") (pinfunction "8_8") (pintype "unspecified"))
      (node (ref "U25") (pin "1") (pinfunction "1_1") (pintype "unspecified"))
      (node (ref "U25") (pin "7") (pinfunction "7_7") (pintype "unspecified"))
      (node (ref "U25") (pin "8") (pinfunction "8_8") (pintype "unspecified"))
      (node (ref "U6") (pin "15") (pinfunction "15_15") (pintype "unspecified"))
      (node (ref "U7") (pin "1") (pinfunction "1_1") (pintype "unspecified"))
      (node (ref "U7") (pin "12") (pinfunction "12_12") (pintype "unspecified"))
      (node (ref "U7") (pin "15") (pinfunction "15_15") (pintype "unspecified"))
      (node (ref "U9") (pin "12") (pinfunction "VSSA_12") (pintype "unspecified"))
      (node (ref "U9") (pin "18") (pinfunction "VSS_18") (pintype "unspecified"))
      (node (ref "U9") (pin "31") (pinfunction "VSS_31") (pintype "unspecified"))
      (node (ref "U9") (pin "47") (pinfunction "VSS_47") (pintype "unspecified"))
      (node (ref "U9") (pin "63") (pinfunction "VSS_63") (pintype "unspecified"))
      (node (ref "adc6") (pin "1") (pinfunction "1_1") (pintype "unspecified"))
      (node (ref "adc6") (pin "5") (pinfunction "5_5") (pintype "unspecified"))
      (node (ref "adc6") (pin "6") (pinfunction "6_6") (pintype "unspecified"))
      (node (ref "tof5") (pin "1") (pinfunction "1_1") (pintype "unspecified"))
      (node (ref "tof5") (pin "5") (pinfunction "5_5") (pintype "unspecified"))
      (node (ref "tof5") (pin "6") (pinfunction "6_6") (pintype "unspecified"))
    )
    (net (code "16") (name "JTCK_SWCLK") (class "Default")
      (node (ref "R67") (pin "1") (pinfunction "1_1") (pintype "input"))
      (node (ref "U9") (pin "49") (pinfunction "PA14_49") (pintype "unspecified"))
    )
    (net (code "17") (name "JTDI") (class "Default")
      (node (ref "R63") (pin "1") (pinfunction "1_1") (pintype "input"))
      (node (ref "U9") (pin "50") (pinfunction "PA15_50") (pintype "unspecified"))
    )
    (net (code "18") (name "JTDO") (class "Default")
      (node (ref "R64") (pin "1") (pinfunction "1_1") (pintype "input"))
      (node (ref "U9") (pin "55") (pinfunction "PB3_55") (pintype "unspecified"))
    )
    (net (code "19") (name "JTMS_SWDIO") (class "Default")
      (node (ref "R68") (pin "1") (pinfunction "1_1") (pintype "input"))
      (node (ref "U9") (pin "46") (pinfunction "PA13_46") (pintype "unspecified"))
    )
    (net (code "20") (name "MODEM_RX") (class "Default")
      (node (ref "R53") (pin "2") (pinfunction "2_2") (pintype "input"))
      (node (ref "U9") (pin "52") (pinfunction "PC11_52") (pintype "unspecified"))
    )
    (net (code "21") (name "MODEM_TX") (class "Default")
      (node (ref "R52") (pin "2") (pinfunction "2_2") (pintype "input"))
      (node (ref "U9") (pin "51") (pinfunction "PC10_51") (pintype "unspecified"))
    )
    (net (code "22") (name "NJTRST") (class "Default")
      (node (ref "U9") (pin "56") (pinfunction "PB4_56") (pintype "unspecified"))
    )
    (net (code "23") (name "NRST") (class "Default")
      (node (ref "C52") (pin "2") (pinfunction "2_2") (pintype "unspecified"))
      (node (ref "NRST1") (pin "1") (pinfunction "1_1") (pintype "unspecified"))
      (node (ref "NRST1") (pin "2") (pinfunction "2_2") (pintype "unspecified"))
      (node (ref "R62") (pin "1") (pinfunction "1_1") (pintype "input"))
      (node (ref "U9") (pin "7") (pinfunction "NRST_7") (pintype "unspecified"))
    )
    (net (code "24") (name "Net-(ADC24-Pad2)") (class "Default")
      (node (ref "ADC24") (pin "2") (pinfunction "2_2") (pintype "unspecified"))
      (node (ref "R46") (pin "2") (pinfunction "2_2") (pintype "input"))
    )
    (net (code "25") (name "Net-(ADC24-Pad3)") (class "Default")
      (node (ref "ADC24") (pin "3") (pinfunction "3_3") (pintype "unspecified"))
      (node (ref "R47") (pin "2") (pinfunction "2_2") (pintype "input"))
    )
    (net (code "26") (name "Net-(ADC24-Pad4)") (class "Default")
      (node (ref "ADC24") (pin "4") (pinfunction "4_4") (pintype "unspecified"))
      (node (ref "R48") (pin "2") (pinfunction "2_2") (pintype "input"))
    )
    (net (code "27") (name "Net-(ADC24-Pad5)") (class "Default")
      (node (ref "ADC24") (pin "5") (pinfunction "5_5") (pintype "unspecified"))
      (node (ref "R49") (pin "2") (pinfunction "2_2") (pintype "input"))
    )
    (net (code "28") (name "Net-(BAT3-Pad1)") (class "Default")
      (node (ref "BAT3") (pin "1") (pinfunction "1_1") (pintype "unspecified"))
      (node (ref "D7") (pin "2") (pinfunction "2_2") (pintype "unspecified"))
      (node (ref "F1") (pin "2") (pinfunction "2_2") (pintype "unspecified"))
    )
    (net (code "29") (name "Net-(C2-Pad1)") (class "Default")
      (node (ref "C2") (pin "1") (pinfunction "1_1") (pintype "unspecified"))
      (node (ref "C5") (pin "1") (pinfunction "1_1") (pintype "unspecified"))
      (node (ref "U9") (pin "30") (pinfunction "VCAP_30") (pintype "unspecified"))
      (node (ref "U9") (pin "62") (pinfunction "VCAP_62") (pintype "unspecified"))
    )
    (net (code "30") (name "Net-(C65-Pad1)") (class "Default")
      (node (ref "C65") (pin "1") (pinfunction "1_1") (pintype "input"))
      (node (ref "R74") (pin "2") (pinfunction "2_2") (pintype "input"))
    )
    (net (code "31") (name "Net-(C66-Pad1)") (class "Default")
      (node (ref "C66") (pin "1") (pinfunction "1_1") (pintype "input"))
      (node (ref "R73") (pin "2") (pinfunction "2_2") (pintype "input"))
    )
    (net (code "32") (name "Net-(D8-Pad2)") (class "Default")
      (node (ref "D8") (pin "2") (pinfunction "2_2") (pintype "unspecified"))
      (node (ref "R30") (pin "2") (pinfunction "2_2") (pintype "input"))
      (node (ref "SERVO2") (pin "6") (pinfunction "6_6") (pintype "unspecified"))
    )
    (net (code "33") (name "Net-(D9-Pad2)") (class "Default")
      (node (ref "D9") (pin "2") (pinfunction "2_2") (pintype "unspecified"))
      (node (ref "R29") (pin "2") (pinfunction "2_2") (pintype "input"))
      (node (ref "SERVO2") (pin "5") (pinfunction "5_5") (pintype "unspecified"))
    )
    (net (code "34") (name "Net-(D10-Pad2)") (class "Default")
      (node (ref "D10") (pin "2") (pinfunction "2_2") (pintype "unspecified"))
      (node (ref "R28") (pin "2") (pinfunction "2_2") (pintype "input"))
      (node (ref "SERVO2") (pin "4") (pinfunction "4_4") (pintype "unspecified"))
    )
    (net (code "35") (name "Net-(D11-Pad2)") (class "Default")
      (node (ref "D11") (pin "2") (pinfunction "2_2") (pintype "unspecified"))
      (node (ref "R27") (pin "2") (pinfunction "2_2") (pintype "input"))
      (node (ref "SERVO2") (pin "3") (pinfunction "3_3") (pintype "unspecified"))
    )
    (net (code "36") (name "Net-(D12-Pad2)") (class "Default")
      (node (ref "D12") (pin "2") (pinfunction "2_2") (pintype "unspecified"))
      (node (ref "R26") (pin "2") (pinfunction "2_2") (pintype "input"))
      (node (ref "SERVO2") (pin "2") (pinfunction "2_2") (pintype "unspecified"))
    )
    (net (code "37") (name "Net-(D13-Pad2)") (class "Default")
      (node (ref "D13") (pin "2") (pinfunction "2_2") (pintype "unspecified"))
      (node (ref "R25") (pin "2") (pinfunction "2_2") (pintype "input"))
      (node (ref "SERVO2") (pin "1") (pinfunction "1_1") (pintype "unspecified"))
    )
    (net (code "38") (name "Net-(D14-Pad2)") (class "Default")
      (node (ref "D14") (pin "2") (pinfunction "2_2") (pintype "unspecified"))
      (node (ref "H1") (pin "1") (pinfunction "1_1") (pintype "unspecified"))
      (node (ref "R53") (pin "1") (pinfunction "1_1") (pintype "input"))
      (node (ref "U7") (pin "5") (pinfunction "5_5") (pintype "unspecified"))
    )
    (net (code "39") (name "Net-(D15-Pad2)") (class "Default")
      (node (ref "D15") (pin "2") (pinfunction "2_2") (pintype "unspecified"))
      (node (ref "H1") (pin "2") (pinfunction "2_2") (pintype "unspecified"))
      (node (ref "R52") (pin "1") (pinfunction "1_1") (pintype "input"))
      (node (ref "U7") (pin "4") (pinfunction "4_4") (pintype "unspecified"))
    )
    (net (code "40") (name "Net-(D16-Pad2)") (class "Default")
      (node (ref "D16") (pin "2") (pinfunction "2_2") (pintype "unspecified"))
      (node (ref "H2") (pin "4") (pinfunction "4_4") (pintype "unspecified"))
      (node (ref "R68") (pin "2") (pinfunction "2_2") (pintype "input"))
    )
    (net (code "41") (name "Net-(D17-Pad2)") (class "Default")
      (node (ref "D17") (pin "2") (pinfunction "2_2") (pintype "unspecified"))
      (node (ref "H2") (pin "6") (pinfunction "6_6") (pintype "unspecified"))
      (node (ref "R67") (pin "2") (pinfunction "2_2") (pintype "input"))
    )
    (net (code "42") (name "Net-(H2-Pad8)") (class "Default")
      (node (ref "H2") (pin "8") (pinfunction "8_8") (pintype "unspecified"))
      (node (ref "R64") (pin "2") (pinfunction "2_2") (pintype "input"))
    )
    (net (code "43") (name "Net-(H2-Pad10)") (class "Default")
      (node (ref "H2") (pin "10") (pinfunction "10_10") (pintype "unspecified"))
      (node (ref "R63") (pin "2") (pinfunction "2_2") (pintype "input"))
    )
    (net (code "44") (name "Net-(H2-Pad12)") (class "Default")
      (node (ref "H2") (pin "12") (pinfunction "12_12") (pintype "unspecified"))
      (node (ref "R62") (pin "2") (pinfunction "2_2") (pintype "input"))
    )
    (net (code "45") (name "Net-(H2-Pad13)") (class "Default")
      (node (ref "H2") (pin "13") (pinfunction "13_13") (pintype "unspecified"))
      (node (ref "R60") (pin "1") (pinfunction "1_1") (pintype "input"))
    )
    (net (code "46") (name "Net-(H2-Pad14)") (class "Default")
      (node (ref "H2") (pin "14") (pinfunction "14_14") (pintype "unspecified"))
      (node (ref "R61") (pin "2") (pinfunction "2_2") (pintype "input"))
    )
    (net (code "47") (name "Net-(LED1-A)") (class "Default")
      (node (ref "LED1") (pin "2") (pinfunction "A_2") (pintype "unspecified"))
      (node (ref "R1") (pin "1") (pinfunction "1_1") (pintype "input"))
    )
    (net (code "48") (name "Net-(LED1-K)") (class "Default")
      (node (ref "LED1") (pin "1") (pinfunction "K_1") (pintype "unspecified"))
      (node (ref "U10") (pin "7") (pinfunction "PG_7") (pintype "unspecified"))
    )
    (net (code "49") (name "Net-(LED2-A)") (class "Default")
      (node (ref "LED2") (pin "2") (pinfunction "A_2") (pintype "unspecified"))
      (node (ref "R4") (pin "1") (pinfunction "1_1") (pintype "input"))
    )
    (net (code "50") (name "Net-(LED2-K)") (class "Default")
      (node (ref "LED2") (pin "1") (pinfunction "K_1") (pintype "unspecified"))
      (node (ref "U11") (pin "7") (pinfunction "PG_7") (pintype "unspecified"))
    )
    (net (code "51") (name "Net-(LED3-A)") (class "Default")
      (node (ref "LED3") (pin "2") (pinfunction "A_2") (pintype "unspecified"))
      (node (ref "R7") (pin "1") (pinfunction "1_1") (pintype "input"))
    )
    (net (code "52") (name "Net-(LED3-K)") (class "Default")
      (node (ref "LED3") (pin "1") (pinfunction "K_1") (pintype "unspecified"))
      (node (ref "U2") (pin "8") (pinfunction "nFault_8") (pintype "unspecified"))
    )
    (net (code "53") (name "Net-(LED4-CKL)") (class "Default")
      (node (ref "LED4") (pin "4") (pinfunction "CKL_4") (pintype "unspecified"))
      (node (ref "LED5") (pin "6") (pinfunction "CKO_6") (pintype "unspecified"))
    )
    (net (code "54") (name "Net-(LED4-SDI)") (class "Default")
      (node (ref "LED4") (pin "3") (pinfunction "SDI_3") (pintype "unspecified"))
      (node (ref "LED5") (pin "1") (pinfunction "SDO_1") (pintype "unspecified"))
    )
    (net (code "55") (name "Net-(LED5-CKL)") (class "Default")
      (node (ref "LED5") (pin "4") (pinfunction "CKL_4") (pintype "unspecified"))
      (node (ref "LED6") (pin "6") (pinfunction "CKO_6") (pintype "unspecified"))
    )
    (net (code "56") (name "Net-(LED5-SDI)") (class "Default")
      (node (ref "LED5") (pin "3") (pinfunction "SDI_3") (pintype "unspecified"))
      (node (ref "LED6") (pin "1") (pinfunction "SDO_1") (pintype "unspecified"))
    )
    (net (code "57") (name "Net-(LED6-CKL)") (class "Default")
      (node (ref "LED6") (pin "4") (pinfunction "CKL_4") (pintype "unspecified"))
      (node (ref "LED7") (pin "6") (pinfunction "CKO_6") (pintype "unspecified"))
    )
    (net (code "58") (name "Net-(LED6-SDI)") (class "Default")
      (node (ref "LED6") (pin "3") (pinfunction "SDI_3") (pintype "unspecified"))
      (node (ref "LED7") (pin "1") (pinfunction "SDO_1") (pintype "unspecified"))
    )
    (net (code "59") (name "Net-(LED7-CKL)") (class "Default")
      (node (ref "LED7") (pin "4") (pinfunction "CKL_4") (pintype "unspecified"))
      (node (ref "LED8") (pin "6") (pinfunction "CKO_6") (pintype "unspecified"))
    )
    (net (code "60") (name "Net-(LED7-SDI)") (class "Default")
      (node (ref "LED7") (pin "3") (pinfunction "SDI_3") (pintype "unspecified"))
      (node (ref "LED8") (pin "1") (pinfunction "SDO_1") (pintype "unspecified"))
    )
    (net (code "61") (name "Net-(LED8-CKL)") (class "Default")
      (node (ref "LED8") (pin "4") (pinfunction "CKL_4") (pintype "unspecified"))
      (node (ref "LED9") (pin "6") (pinfunction "CKO_6") (pintype "unspecified"))
    )
    (net (code "62") (name "Net-(LED8-SDI)") (class "Default")
      (node (ref "LED8") (pin "3") (pinfunction "SDI_3") (pintype "unspecified"))
      (node (ref "LED9") (pin "1") (pinfunction "SDO_1") (pintype "unspecified"))
    )
    (net (code "63") (name "Net-(LED10-CKL)") (class "Default")
      (node (ref "LED10") (pin "4") (pinfunction "CKL_4") (pintype "unspecified"))
      (node (ref "LED11") (pin "6") (pinfunction "CKO_6") (pintype "unspecified"))
    )
    (net (code "64") (name "Net-(LED10-CKO)") (class "Default")
      (node (ref "LED10") (pin "6") (pinfunction "CKO_6") (pintype "unspecified"))
      (node (ref "LED9") (pin "4") (pinfunction "CKL_4") (pintype "unspecified"))
    )
    (net (code "65") (name "Net-(LED10-SDI)") (class "Default")
      (node (ref "LED10") (pin "3") (pinfunction "SDI_3") (pintype "unspecified"))
      (node (ref "LED11") (pin "1") (pinfunction "SDO_1") (pintype "unspecified"))
    )
    (net (code "66") (name "Net-(LED10-SDO)") (class "Default")
      (node (ref "LED10") (pin "1") (pinfunction "SDO_1") (pintype "unspecified"))
      (node (ref "LED9") (pin "3") (pinfunction "SDI_3") (pintype "unspecified"))
    )
    (net (code "67") (name "Net-(LED11-CKL)") (class "Default")
      (node (ref "LED11") (pin "4") (pinfunction "CKL_4") (pintype "unspecified"))
      (node (ref "R22") (pin "2") (pinfunction "2_2") (pintype "input"))
    )
    (net (code "68") (name "Net-(LED11-SDI)") (class "Default")
      (node (ref "LED11") (pin "3") (pinfunction "SDI_3") (pintype "unspecified"))
      (node (ref "R21") (pin "2") (pinfunction "2_2") (pintype "input"))
    )
    (net (code "69") (name "Net-(R44-Pad2)") (class "Default")
      (node (ref "R44") (pin "2") (pinfunction "2_2") (pintype "input"))
      (node (ref "tof5") (pin "3") (pinfunction "3_3") (pintype "unspecified"))
    )
    (net (code "70") (name "Net-(R45-Pad2)") (class "Default")
      (node (ref "R45") (pin "2") (pinfunction "2_2") (pintype "input"))
      (node (ref "tof5") (pin "2") (pinfunction "2_2") (pintype "unspecified"))
    )
    (net (code "71") (name "Net-(R50-Pad2)") (class "Default")
      (node (ref "R50") (pin "2") (pinfunction "2_2") (pintype "input"))
      (node (ref "adc6") (pin "2") (pinfunction "2_2") (pintype "unspecified"))
    )
    (net (code "72") (name "Net-(R51-Pad2)") (class "Default")
      (node (ref "R51") (pin "2") (pinfunction "2_2") (pintype "input"))
      (node (ref "adc6") (pin "3") (pinfunction "3_3") (pintype "unspecified"))
    )
    (net (code "73") (name "Net-(U2-AISEN)") (class "Default")
      (node (ref "U16") (pin "2") (pinfunction "2_2") (pintype "unspecified"))
      (node (ref "U2") (pin "3") (pinfunction "AISEN_3") (pintype "unspecified"))
    )
    (net (code "74") (name "Net-(U2-AOUT1)") (class "Default")
      (node (ref "R73") (pin "1") (pinfunction "1_1") (pintype "input"))
      (node (ref "U2") (pin "2") (pinfunction "AOUT1_2") (pintype "unspecified"))
      (node (ref "U24") (pin "6") (pinfunction "6_6") (pintype "unspecified"))
    )
    (net (code "75") (name "Net-(U2-AOUT2)") (class "Default")
      (node (ref "C66") (pin "2") (pinfunction "2_2") (pintype "input"))
      (node (ref "U2") (pin "4") (pinfunction "AOUT2_4") (pintype "unspecified"))
      (node (ref "U24") (pin "2") (pinfunction "2_2") (pintype "unspecified"))
    )
    (net (code "76") (name "Net-(U2-BISEN)") (class "Default")
      (node (ref "U17") (pin "2") (pinfunction "2_2") (pintype "unspecified"))
      (node (ref "U2") (pin "6") (pinfunction "BISEN_6") (pintype "unspecified"))
    )
    (net (code "77") (name "Net-(U2-BOUT1)") (class "Default")
      (node (ref "C65") (pin "2") (pinfunction "2_2") (pintype "input"))
      (node (ref "U2") (pin "7") (pinfunction "BOUT1_7") (pintype "unspecified"))
      (node (ref "U25") (pin "2") (pinfunction "2_2") (pintype "unspecified"))
    )
    (net (code "78") (name "Net-(U2-BOUT2)") (class "Default")
      (node (ref "R74") (pin "1") (pinfunction "1_1") (pintype "input"))
      (node (ref "U2") (pin "5") (pinfunction "BOUT2_5") (pintype "unspecified"))
      (node (ref "U25") (pin "6") (pinfunction "6_6") (pintype "unspecified"))
    )
    (net (code "79") (name "Net-(U2-VCP)") (class "Default")
      (node (ref "C35") (pin "2") (pinfunction "2_2") (pintype "input"))
      (node (ref "U2") (pin "11") (pinfunction "VCP_11") (pintype "unspecified"))
    )
    (net (code "80") (name "Net-(U2-VINT)") (class "Default")
      (node (ref "C34") (pin "2") (pinfunction "2_2") (pintype "unspecified"))
      (node (ref "U2") (pin "14") (pinfunction "VINT_14") (pintype "unspecified"))
    )
    (net (code "81") (name "Net-(U2-nSleep)") (class "Default")
      (node (ref "C63") (pin "2") (pinfunction "2_2") (pintype "unspecified"))
      (node (ref "R11") (pin "1") (pinfunction "1_1") (pintype "input"))
      (node (ref "U2") (pin "1") (pinfunction "nSleep_1") (pintype "unspecified"))
    )
    (net (code "82") (name "Net-(U9-PA6)") (class "Default")
      (node (ref "R33") (pin "2") (pinfunction "2_2") (pintype "input"))
      (node (ref "U9") (pin "22") (pinfunction "PA6_22") (pintype "unspecified"))
    )
    (net (code "83") (name "Net-(U9-PA7)") (class "Default")
      (node (ref "R32") (pin "2") (pinfunction "2_2") (pintype "input"))
      (node (ref "U9") (pin "23") (pinfunction "PA7_23") (pintype "unspecified"))
    )
    (net (code "84") (name "Net-(U9-PC6)") (class "Default")
      (node (ref "R36") (pin "1") (pinfunction "1_1") (pintype "input"))
      (node (ref "U9") (pin "37") (pinfunction "PC6_37") (pintype "unspecified"))
    )
    (net (code "85") (name "Net-(U9-PC7)") (class "Default")
      (node (ref "R35") (pin "1") (pinfunction "1_1") (pintype "input"))
      (node (ref "U9") (pin "38") (pinfunction "PC7_38") (pintype "unspecified"))
    )
    (net (code "86") (name "Net-(U10-FB)") (class "Default")
      (node (ref "R2") (pin "2") (pinfunction "2_2") (pintype "input"))
      (node (ref "R3") (pin "1") (pinfunction "1_1") (pintype "unspecified"))
      (node (ref "U10") (pin "6") (pinfunction "FB_6") (pintype "unspecified"))
    )
    (net (code "87") (name "Net-(U10-SS{slash}TR)") (class "Default")
      (node (ref "C25") (pin "2") (pinfunction "2_2") (pintype "unspecified"))
      (node (ref "U10") (pin "8") (pinfunction "SS/TR_8") (pintype "unspecified"))
    )
    (net (code "88") (name "Net-(U11-FB)") (class "Default")
      (node (ref "R5") (pin "2") (pinfunction "2_2") (pintype "input"))
      (node (ref "R6") (pin "1") (pinfunction "1_1") (pintype "unspecified"))
      (node (ref "U11") (pin "6") (pinfunction "FB_6") (pintype "unspecified"))
    )
    (net (code "89") (name "Net-(U11-SS{slash}TR)") (class "Default")
      (node (ref "C28") (pin "2") (pinfunction "2_2") (pintype "unspecified"))
      (node (ref "U11") (pin "8") (pinfunction "SS/TR_8") (pintype "unspecified"))
    )
    (net (code "90") (name "Net-(U18-I2C_RST)") (class "Default")
      (node (ref "R12") (pin "2") (pinfunction "2_2") (pintype "input"))
      (node (ref "U18") (pin "A1") (pinfunction "I2C_RST_A1") (pintype "unspecified"))
    )
    (net (code "91") (name "Net-(U18-INT)") (class "Default")
      (node (ref "R10") (pin "1") (pinfunction "1_1") (pintype "input"))
      (node (ref "U18") (pin "A3") (pinfunction "INT_A3") (pintype "unspecified"))
    )
    (net (code "92") (name "Net-(U18-LPn)") (class "Default")
      (node (ref "R13") (pin "1") (pinfunction "1_1") (pintype "input"))
      (node (ref "U18") (pin "A5") (pinfunction "LPn_A5") (pintype "unspecified"))
    )
    (net (code "93") (name "Net-(U18-RSVD6)") (class "Default")
      (node (ref "R14") (pin "1") (pinfunction "1_1") (pintype "input"))
      (node (ref "U18") (pin "C2") (pinfunction "RSVD6_C2") (pintype "unspecified"))
    )
    (net (code "94") (name "PWM1") (class "Default")
      (node (ref "U2") (pin "16") (pinfunction "AIN1_16") (pintype "unspecified"))
      (node (ref "U9") (pin "14") (pinfunction "PA0_14") (pintype "unspecified"))
    )
    (net (code "95") (name "PWM2") (class "Default")
      (node (ref "U2") (pin "9") (pinfunction "BIN1_9") (pintype "unspecified"))
      (node (ref "U9") (pin "15") (pinfunction "PA1_15") (pintype "unspecified"))
    )
    (net (code "96") (name "RGB_MOSI") (class "Default")
      (node (ref "R21") (pin "1") (pinfunction "1_1") (pintype "input"))
      (node (ref "U9") (pin "36") (pinfunction "PB15_36") (pintype "unspecified"))
    )
    (net (code "97") (name "RGB_SCK") (class "Default")
      (node (ref "R22") (pin "1") (pinfunction "1_1") (pintype "input"))
      (node (ref "U9") (pin "34") (pinfunction "PB13_34") (pintype "unspecified"))
    )
    (net (code "98") (name "SENS1") (class "Default")
      (node (ref "U2") (pin "15") (pinfunction "AIN2_15") (pintype "unspecified"))
      (node (ref "U9") (pin "29") (pinfunction "PB10_29") (pintype "unspecified"))
    )
    (net (code "99") (name "SENS2") (class "Default")
      (node (ref "U2") (pin "10") (pinfunction "BIN2_10") (pintype "unspecified"))
      (node (ref "U9") (pin "28") (pinfunction "PB2_28") (pintype "unspecified"))
    )
    (net (code "100") (name "SERVO1") (class "Default")
      (node (ref "R25") (pin "1") (pinfunction "1_1") (pintype "input"))
      (node (ref "U9") (pin "16") (pinfunction "PA2_16") (pintype "unspecified"))
    )
    (net (code "101") (name "SERVO2") (class "Default")
      (node (ref "R26") (pin "1") (pinfunction "1_1") (pintype "input"))
      (node (ref "U9") (pin "17") (pinfunction "PA3_17") (pintype "unspecified"))
    )
    (net (code "102") (name "SERVO3") (class "Default")
      (node (ref "R27") (pin "1") (pinfunction "1_1") (pintype "input"))
      (node (ref "U9") (pin "35") (pinfunction "PB14_35") (pintype "unspecified"))
    )
    (net (code "103") (name "SERVO4") (class "Default")
      (node (ref "R28") (pin "1") (pinfunction "1_1") (pintype "input"))
      (node (ref "U9") (pin "42") (pinfunction "PA9_42") (pintype "unspecified"))
    )
    (net (code "104") (name "SERVO5") (class "Default")
      (node (ref "R29") (pin "1") (pinfunction "1_1") (pintype "input"))
      (node (ref "U9") (pin "44") (pinfunction "PA11_44") (pintype "unspecified"))
    )
    (net (code "105") (name "SERVO6") (class "Default")
      (node (ref "R30") (pin "1") (pinfunction "1_1") (pintype "input"))
      (node (ref "U9") (pin "10") (pinfunction "PC2_10") (pintype "unspecified"))
    )
    (net (code "106") (name "TOF1_SCL") (class "Default")
      (node (ref "R9") (pin "1") (pinfunction "1_1") (pintype "input"))
      (node (ref "U18") (pin "C4") (pinfunction "SCL_C4") (pintype "unspecified"))
      (node (ref "U9") (pin "61") (pinfunction "PB8_61") (pintype "unspecified"))
    )
    (net (code "107") (name "TOF1_SDA") (class "Default")
      (node (ref "R8") (pin "1") (pinfunction "1_1") (pintype "input"))
      (node (ref "U18") (pin "C3") (pinfunction "SDA_C3") (pintype "unspecified"))
      (node (ref "U9") (pin "59") (pinfunction "PB7_59") (pintype "unspecified"))
    )
    (net (code "108") (name "TOF2_SCL") (class "Default")
      (node (ref "R44") (pin "1") (pinfunction "1_1") (pintype "input"))
      (node (ref "U9") (pin "41") (pinfunction "PA8_41") (pintype "unspecified"))
    )
    (net (code "109") (name "TOF2_SDA") (class "Default")
      (node (ref "R45") (pin "1") (pinfunction "1_1") (pintype "input"))
      (node (ref "U9") (pin "40") (pinfunction "PC9_40") (pintype "unspecified"))
    )
    (net (code "110") (name "USART1_RX") (class "Default")
      (node (ref "R60") (pin "2") (pinfunction "2_2") (pintype "input"))
      (node (ref "U9") (pin "43") (pinfunction "PA10_43") (pintype "unspecified"))
    )
    (net (code "111") (name "USART1_TX") (class "Default")
      (node (ref "R61") (pin "1") (pinfunction "1_1") (pintype "input"))
      (node (ref "U9") (pin "58") (pinfunction "PB6_58") (pintype "unspecified"))
    )
    (net (code "112") (name "VBAT_VSENS") (class "Default")
      (node (ref "C51") (pin "2") (pinfunction "2_2") (pintype "unspecified"))
      (node (ref "R23") (pin "2") (pinfunction "2_2") (pintype "input"))
      (node (ref "R24") (pin "1") (pinfunction "1_1") (pintype "input"))
      (node (ref "U9") (pin "21") (pinfunction "PA5_21") (pintype "unspecified"))
    )
    (net (code "113") (name "VIN") (class "Default")
      (node (ref "C26") (pin "2") (pinfunction "2_2") (pintype "unspecified"))
      (node (ref "C29") (pin "2") (pinfunction "2_2") (pintype "unspecified"))
      (node (ref "C32") (pin "2") (pinfunction "2_2") (pintype "unspecified"))
      (node (ref "C33") (pin "2") (pinfunction "2_2") (pintype "unspecified"))
      (node (ref "C35") (pin "1") (pinfunction "1_1") (pintype "input"))
      (node (ref "F1") (pin "1") (pinfunction "1_1") (pintype "unspecified"))
      (node (ref "R24") (pin "2") (pinfunction "2_2") (pintype "input"))
      (node (ref "U10") (pin "1") (pinfunction "EN_1") (pintype "unspecified"))
      (node (ref "U10") (pin "2") (pinfunction "VIN_2") (pintype "unspecified"))
      (node (ref "U11") (pin "1") (pinfunction "EN_1") (pintype "unspecified"))
      (node (ref "U11") (pin "2") (pinfunction "VIN_2") (pintype "unspecified"))
      (node (ref "U2") (pin "12") (pinfunction "VM_12") (pintype "unspecified"))
      (node (ref "U23") (pin "1") (pinfunction "1_1") (pintype "input"))
    )
    (net (code "114") (name "unconnected-(H2-Pad1)") (class "Default")
      (node (ref "H2") (pin "1") (pinfunction "1_1") (pintype "unspecified+no_connect"))
    )
    (net (code "115") (name "unconnected-(H2-Pad2)") (class "Default")
      (node (ref "H2") (pin "2") (pinfunction "2_2") (pintype "unspecified+no_connect"))
    )
    (net (code "116") (name "unconnected-(H2-Pad9)") (class "Default")
      (node (ref "H2") (pin "9") (pinfunction "9_9") (pintype "unspecified+no_connect"))
    )
    (net (code "117") (name "unconnected-(LED4-CKO-Pad6)") (class "Default")
      (node (ref "LED4") (pin "6") (pinfunction "CKO_6") (pintype "unspecified+no_connect"))
    )
    (net (code "118") (name "unconnected-(LED4-SDO-Pad1)") (class "Default")
      (node (ref "LED4") (pin "1") (pinfunction "SDO_1") (pintype "unspecified+no_connect"))
    )
    (net (code "119") (name "unconnected-(SCREW1-Pad1)") (class "Default")
      (node (ref "SCREW1") (pin "1") (pinfunction "1_1") (pintype "input+no_connect"))
    )
    (net (code "120") (name "unconnected-(SCREW2-Pad1)") (class "Default")
      (node (ref "SCREW2") (pin "1") (pinfunction "1_1") (pintype "input+no_connect"))
    )
    (net (code "121") (name "unconnected-(SCREW3-Pad1)") (class "Default")
      (node (ref "SCREW3") (pin "1") (pinfunction "1_1") (pintype "input+no_connect"))
    )
    (net (code "122") (name "unconnected-(SCREW4-Pad1)") (class "Default")
      (node (ref "SCREW4") (pin "1") (pinfunction "1_1") (pintype "input+no_connect"))
    )
    (net (code "123") (name "unconnected-(U6-Pad2)") (class "Default")
      (node (ref "U6") (pin "2") (pinfunction "2_2") (pintype "unspecified+no_connect"))
    )
    (net (code "124") (name "unconnected-(U6-Pad3)") (class "Default")
      (node (ref "U6") (pin "3") (pinfunction "3_3") (pintype "unspecified+no_connect"))
    )
    (net (code "125") (name "unconnected-(U6-Pad4)") (class "Default")
      (node (ref "U6") (pin "4") (pinfunction "4_4") (pintype "unspecified+no_connect"))
    )
    (net (code "126") (name "unconnected-(U6-Pad5)") (class "Default")
      (node (ref "U6") (pin "5") (pinfunction "5_5") (pintype "unspecified+no_connect"))
    )
    (net (code "127") (name "unconnected-(U6-Pad6)") (class "Default")
      (node (ref "U6") (pin "6") (pinfunction "6_6") (pintype "unspecified+no_connect"))
    )
    (net (code "128") (name "unconnected-(U6-Pad7)") (class "Default")
      (node (ref "U6") (pin "7") (pinfunction "7_7") (pintype "unspecified+no_connect"))
    )
    (net (code "129") (name "unconnected-(U6-Pad8)") (class "Default")
      (node (ref "U6") (pin "8") (pinfunction "8_8") (pintype "unspecified+no_connect"))
    )
    (net (code "130") (name "unconnected-(U6-Pad9)") (class "Default")
      (node (ref "U6") (pin "9") (pinfunction "9_9") (pintype "unspecified+no_connect"))
    )
    (net (code "131") (name "unconnected-(U6-Pad10)") (class "Default")
      (node (ref "U6") (pin "10") (pinfunction "10_10") (pintype "unspecified+no_connect"))
    )
    (net (code "132") (name "unconnected-(U6-Pad11)") (class "Default")
      (node (ref "U6") (pin "11") (pinfunction "11_11") (pintype "unspecified+no_connect"))
    )
    (net (code "133") (name "unconnected-(U6-Pad12)") (class "Default")
      (node (ref "U6") (pin "12") (pinfunction "12_12") (pintype "unspecified+no_connect"))
    )
    (net (code "134") (name "unconnected-(U6-Pad13)") (class "Default")
      (node (ref "U6") (pin "13") (pinfunction "13_13") (pintype "unspecified+no_connect"))
    )
    (net (code "135") (name "unconnected-(U6-Pad14)") (class "Default")
      (node (ref "U6") (pin "14") (pinfunction "14_14") (pintype "unspecified+no_connect"))
    )
    (net (code "136") (name "unconnected-(U6-Pad16)") (class "Default")
      (node (ref "U6") (pin "16") (pinfunction "16_16") (pintype "unspecified+no_connect"))
    )
    (net (code "137") (name "unconnected-(U7-Pad2)") (class "Default")
      (node (ref "U7") (pin "2") (pinfunction "2_2") (pintype "unspecified+no_connect"))
    )
    (net (code "138") (name "unconnected-(U7-Pad3)") (class "Default")
      (node (ref "U7") (pin "3") (pinfunction "3_3") (pintype "unspecified+no_connect"))
    )
    (net (code "139") (name "unconnected-(U7-Pad6)") (class "Default")
      (node (ref "U7") (pin "6") (pinfunction "6_6") (pintype "unspecified+no_connect"))
    )
    (net (code "140") (name "unconnected-(U7-Pad7)") (class "Default")
      (node (ref "U7") (pin "7") (pinfunction "7_7") (pintype "unspecified+no_connect"))
    )
    (net (code "141") (name "unconnected-(U7-Pad8)") (class "Default")
      (node (ref "U7") (pin "8") (pinfunction "8_8") (pintype "unspecified+no_connect"))
    )
    (net (code "142") (name "unconnected-(U7-Pad9)") (class "Default")
      (node (ref "U7") (pin "9") (pinfunction "9_9") (pintype "unspecified+no_connect"))
    )
    (net (code "143") (name "unconnected-(U7-Pad10)") (class "Default")
      (node (ref "U7") (pin "10") (pinfunction "10_10") (pintype "unspecified+no_connect"))
    )
    (net (code "144") (name "unconnected-(U7-Pad11)") (class "Default")
      (node (ref "U7") (pin "11") (pinfunction "11_11") (pintype "unspecified+no_connect"))
    )
    (net (code "145") (name "unconnected-(U7-Pad13)") (class "Default")
      (node (ref "U7") (pin "13") (pinfunction "13_13") (pintype "unspecified+no_connect"))
    )
    (net (code "146") (name "unconnected-(U7-Pad14)") (class "Default")
      (node (ref "U7") (pin "14") (pinfunction "14_14") (pintype "unspecified+no_connect"))
    )
    (net (code "147") (name "unconnected-(U7-Pad16)") (class "Default")
      (node (ref "U7") (pin "16") (pinfunction "16_16") (pintype "unspecified+no_connect"))
    )
    (net (code "148") (name "unconnected-(U9-PA4-Pad20)") (class "Default")
      (node (ref "U9") (pin "20") (pinfunction "PA4_20") (pintype "unspecified+no_connect"))
    )
    (net (code "149") (name "unconnected-(U9-PA12-Pad45)") (class "Default")
      (node (ref "U9") (pin "45") (pinfunction "PA12_45") (pintype "unspecified+no_connect"))
    )
    (net (code "150") (name "unconnected-(U9-PB1-Pad27)") (class "Default")
      (node (ref "U9") (pin "27") (pinfunction "PB1_27") (pintype "unspecified+no_connect"))
    )
    (net (code "151") (name "unconnected-(U9-PB5-Pad57)") (class "Default")
      (node (ref "U9") (pin "57") (pinfunction "PB5_57") (pintype "unspecified+no_connect"))
    )
    (net (code "152") (name "unconnected-(U9-PB12-Pad33)") (class "Default")
      (node (ref "U9") (pin "33") (pinfunction "PB12_33") (pintype "unspecified+no_connect"))
    )
    (net (code "153") (name "unconnected-(U9-PC8-Pad39)") (class "Default")
      (node (ref "U9") (pin "39") (pinfunction "PC8_39") (pintype "unspecified+no_connect"))
    )
    (net (code "154") (name "unconnected-(U9-PC12-Pad53)") (class "Default")
      (node (ref "U9") (pin "53") (pinfunction "PC12_53") (pintype "unspecified+no_connect"))
    )
    (net (code "155") (name "unconnected-(U9-PC13-Pad2)") (class "Default")
      (node (ref "U9") (pin "2") (pinfunction "PC13_2") (pintype "unspecified+no_connect"))
    )
    (net (code "156") (name "unconnected-(U9-PC14-OSC32_IN-Pad3)") (class "Default")
      (node (ref "U9") (pin "3") (pinfunction "PC14-OSC32_IN_3") (pintype "unspecified+no_connect"))
    )
    (net (code "157") (name "unconnected-(U9-PC15-OSC32_OUT-Pad4)") (class "Default")
      (node (ref "U9") (pin "4") (pinfunction "PC15-OSC32_OUT_4") (pintype "unspecified+no_connect"))
    )
    (net (code "158") (name "unconnected-(U9-PD2-Pad54)") (class "Default")
      (node (ref "U9") (pin "54") (pinfunction "PD2_54") (pintype "unspecified+no_connect"))
    )
    (net (code "159") (name "unconnected-(U9-PH0-OSC_IN-Pad5)") (class "Default")
      (node (ref "U9") (pin "5") (pinfunction "PH0-OSC_IN_5") (pintype "unspecified+no_connect"))
    )
    (net (code "160") (name "unconnected-(U9-PH1-OSC_OUT-Pad6)") (class "Default")
      (node (ref "U9") (pin "6") (pinfunction "PH1-OSC_OUT_6") (pintype "unspecified+no_connect"))
    )
    (net (code "161") (name "unconnected-(U18-RSVD5-PadC5)") (class "Default")
      (node (ref "U18") (pin "C5") (pinfunction "RSVD5_C5") (pintype "unspecified+no_connect"))
    )
  )
)
